# galvanika-board-2_2.net
KiCad netlist of a schematic drawn in EAGLE
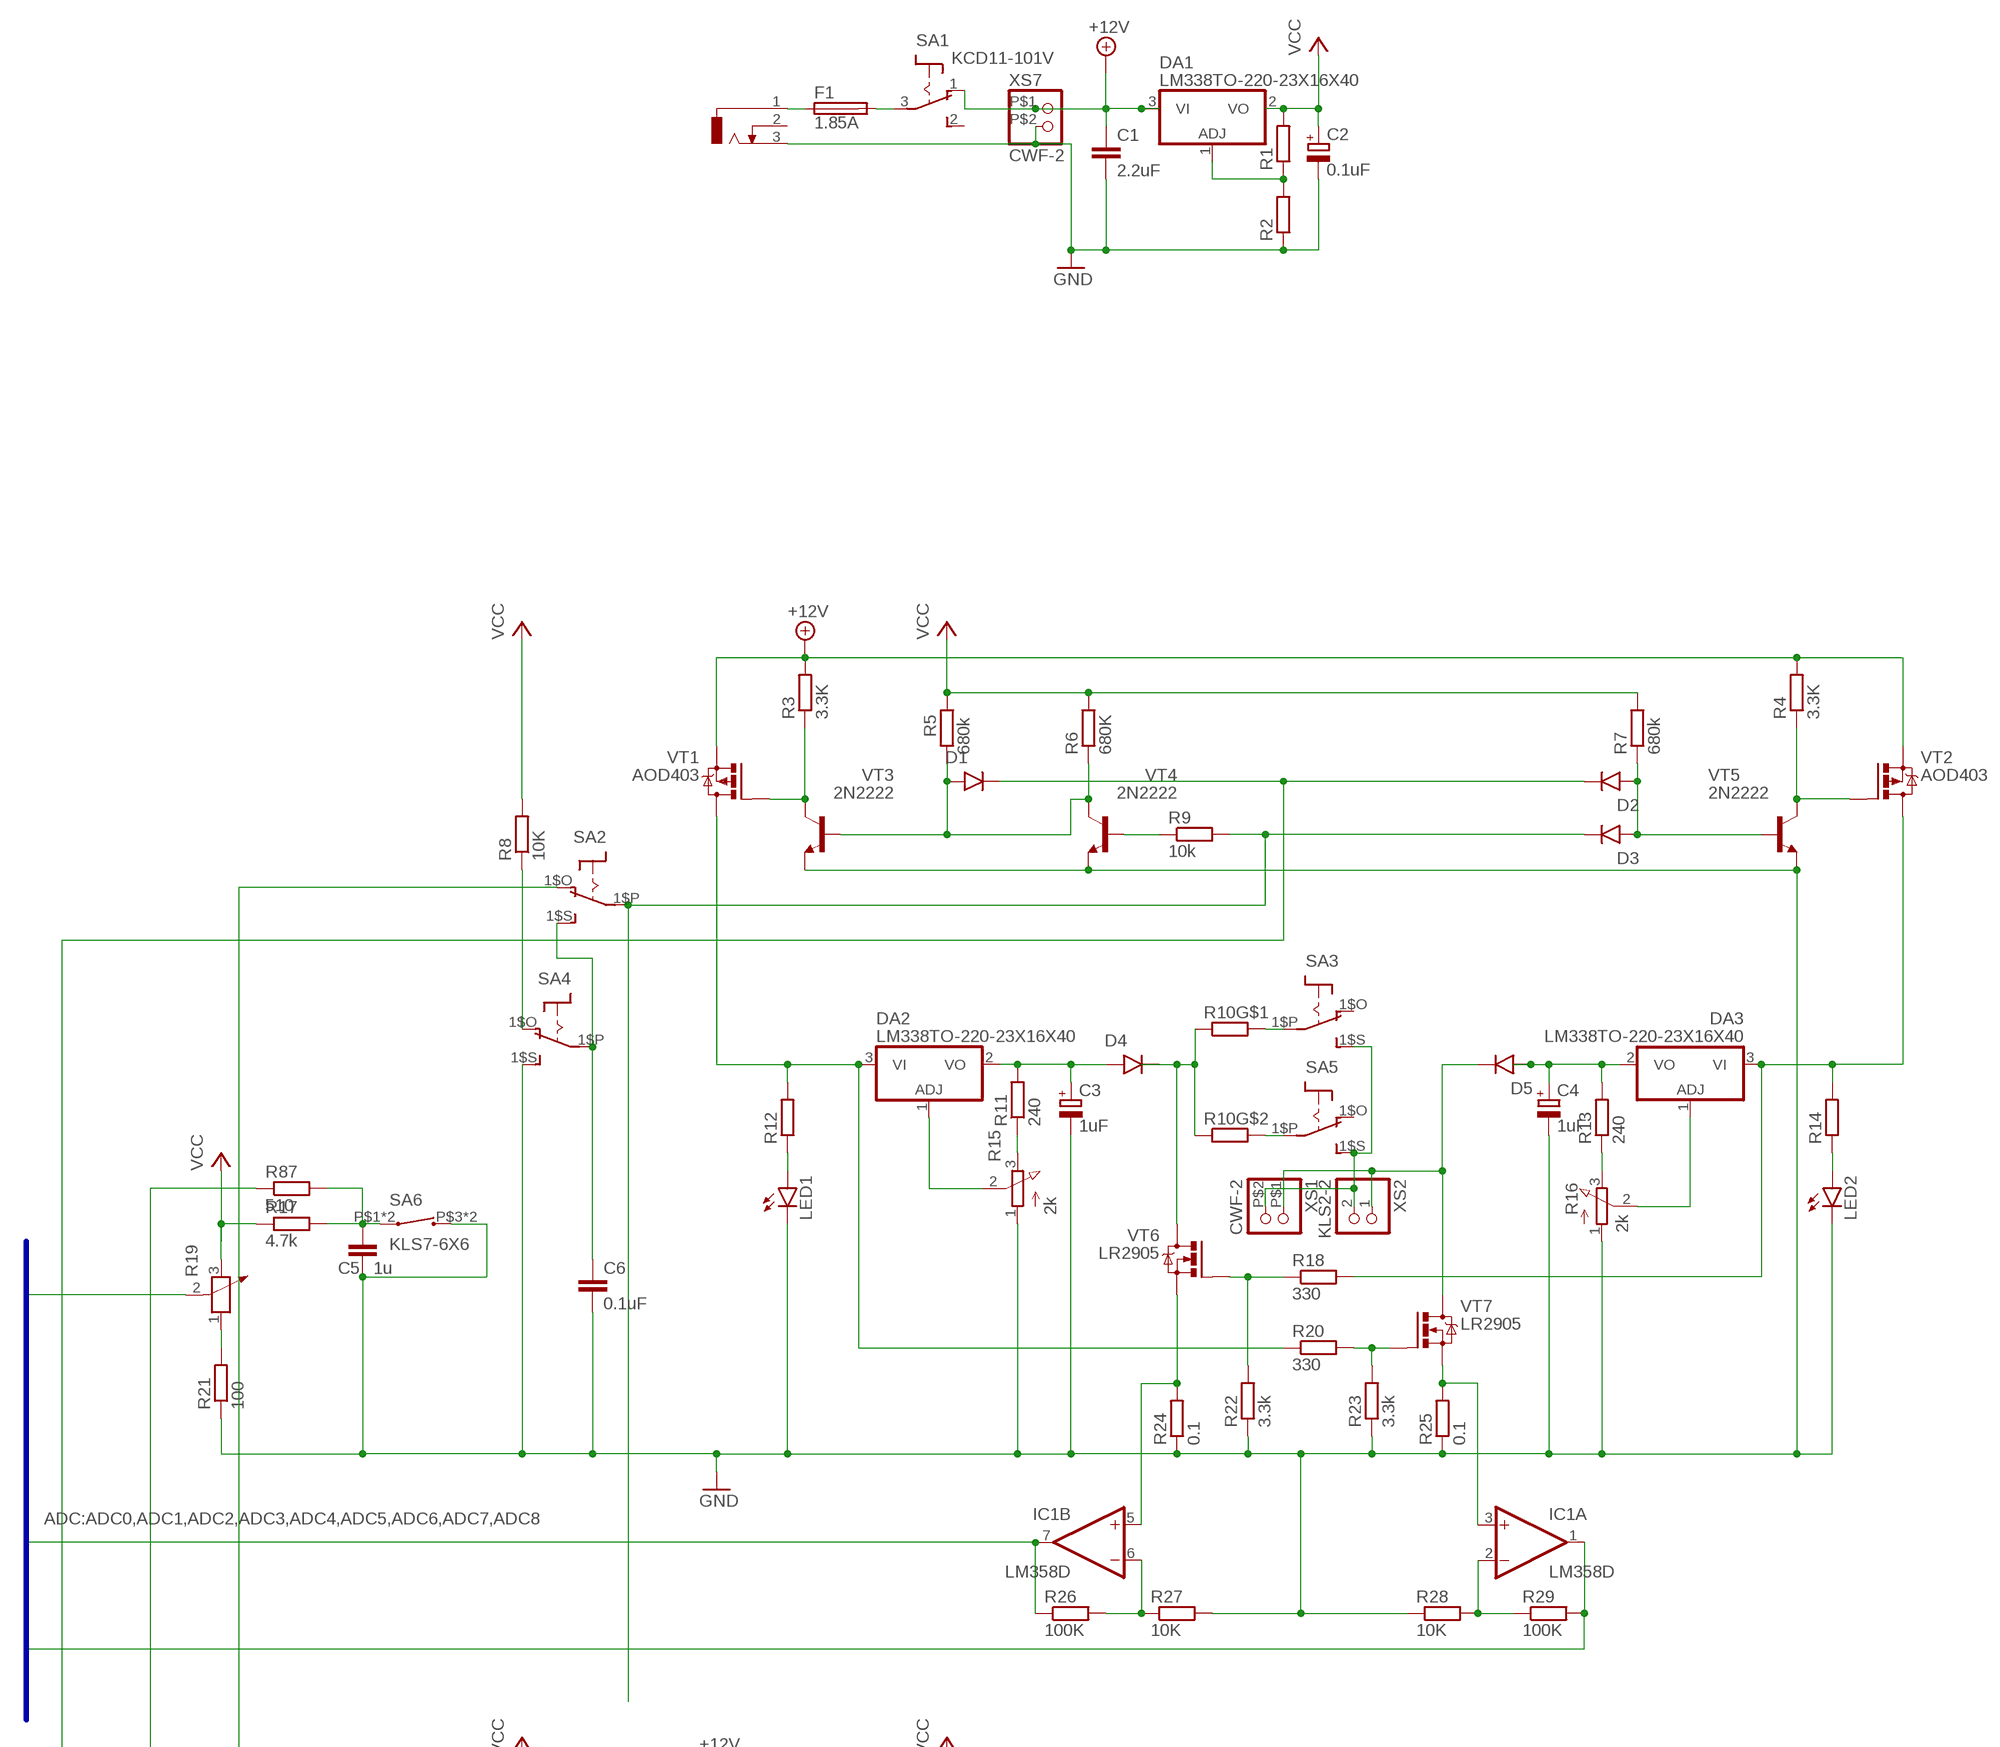
[diagram p0: schematic, sheet 1, part 1 of 2]
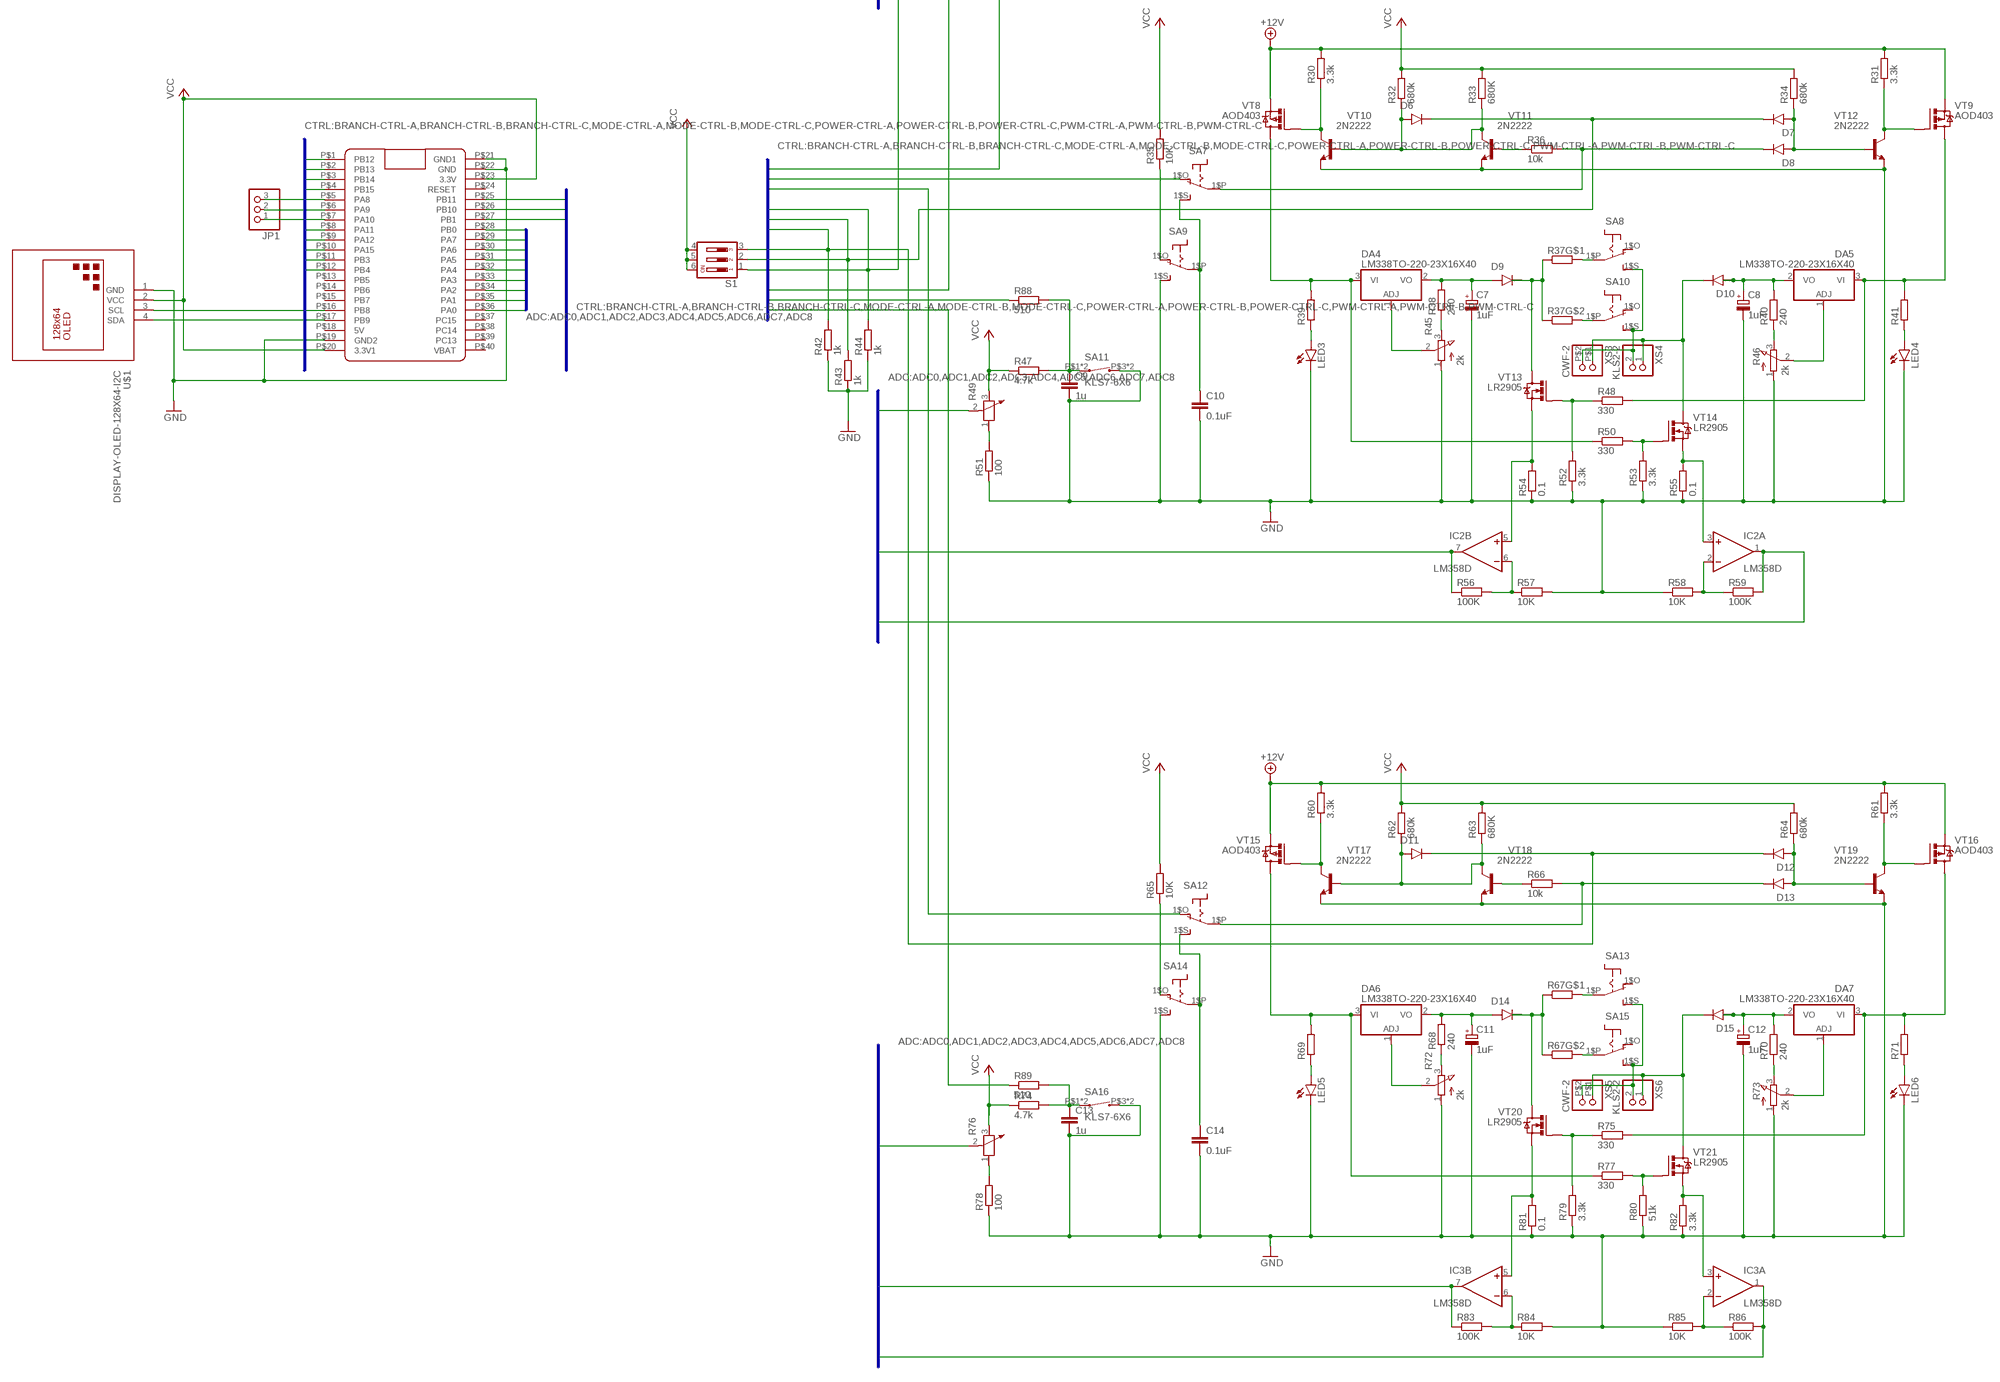
[diagram p1: schematic, sheet 1, part 2 of 2]

(export (version "E")
  (design (tool "Eeschema 10.0.6"))
  (components
    (comp (ref "C1")
      (value "2.2uF")
      (footprint "eagle-import:C025-025X050")
      (libsource (lib "eagle-import") (part "C-EU025-025X050"))
    )
    (comp (ref "C2")
      (value "0.1uF")
      (footprint "eagle-import:E2,5-5")
      (libsource (lib "eagle-import") (part "rcl_334_CPOL-EUE2.5-5"))
    )
    (comp (ref "C3")
      (value "1uF")
      (footprint "eagle-import:E5-4")
      (libsource (lib "eagle-import") (part "CPOL-EUE5-4"))
    )
    (comp (ref "C4")
      (value "1uF")
      (footprint "eagle-import:E5-4")
      (libsource (lib "eagle-import") (part "CPOL-EUE5-4"))
    )
    (comp (ref "C5")
      (value "1u")
      (footprint "eagle-import:C1206")
      (libsource (lib "eagle-import") (part "C-EUC1206"))
    )
    (comp (ref "C6")
      (value "0.1uF")
      (footprint "eagle-import:C1206")
      (libsource (lib "eagle-import") (part "C-EUC1206"))
    )
    (comp (ref "C7")
      (value "1uF")
      (footprint "eagle-import:E5-4")
      (libsource (lib "eagle-import") (part "CPOL-EUE5-4"))
    )
    (comp (ref "C8")
      (value "1uF")
      (footprint "eagle-import:E5-4")
      (libsource (lib "eagle-import") (part "CPOL-EUE5-4"))
    )
    (comp (ref "C9")
      (value "1u")
      (footprint "eagle-import:C1206")
      (libsource (lib "eagle-import") (part "C-EUC1206"))
    )
    (comp (ref "C10")
      (value "0.1uF")
      (footprint "eagle-import:C1206")
      (libsource (lib "eagle-import") (part "C-EUC1206"))
    )
    (comp (ref "C11")
      (value "1uF")
      (footprint "eagle-import:E5-4")
      (libsource (lib "eagle-import") (part "CPOL-EUE5-4"))
    )
    (comp (ref "C12")
      (value "1uF")
      (footprint "eagle-import:E5-4")
      (libsource (lib "eagle-import") (part "CPOL-EUE5-4"))
    )
    (comp (ref "C13")
      (value "1u")
      (footprint "eagle-import:C1206")
      (libsource (lib "eagle-import") (part "C-EUC1206"))
    )
    (comp (ref "C14")
      (value "0.1uF")
      (footprint "eagle-import:C1206")
      (libsource (lib "eagle-import") (part "C-EUC1206"))
    )
    (comp (ref "D1")
      (value "1N4001")
      (footprint "eagle-import:DO41-10")
      (libsource (lib "eagle-import") (part "1N4001"))
    )
    (comp (ref "D2")
      (value "1N4001")
      (footprint "eagle-import:DO41-10")
      (libsource (lib "eagle-import") (part "1N4001"))
    )
    (comp (ref "D3")
      (value "1N4001")
      (footprint "eagle-import:DO41-10")
      (libsource (lib "eagle-import") (part "1N4001"))
    )
    (comp (ref "D4")
      (value "1N4001")
      (footprint "eagle-import:DO41-10")
      (libsource (lib "eagle-import") (part "1N4001"))
    )
    (comp (ref "D5")
      (value "1N4001")
      (footprint "eagle-import:DO41-10")
      (libsource (lib "eagle-import") (part "1N4001"))
    )
    (comp (ref "D6")
      (value "1N4001")
      (footprint "eagle-import:DO41-10")
      (libsource (lib "eagle-import") (part "1N4001"))
    )
    (comp (ref "D7")
      (value "1N4001")
      (footprint "eagle-import:DO41-10")
      (libsource (lib "eagle-import") (part "1N4001"))
    )
    (comp (ref "D8")
      (value "1N4001")
      (footprint "eagle-import:DO41-10")
      (libsource (lib "eagle-import") (part "1N4001"))
    )
    (comp (ref "D9")
      (value "1N4001")
      (footprint "eagle-import:DO41-10")
      (libsource (lib "eagle-import") (part "1N4001"))
    )
    (comp (ref "D10")
      (value "1N4001")
      (footprint "eagle-import:DO41-10")
      (libsource (lib "eagle-import") (part "1N4001"))
    )
    (comp (ref "D11")
      (value "1N4001")
      (footprint "eagle-import:DO41-10")
      (libsource (lib "eagle-import") (part "1N4001"))
    )
    (comp (ref "D12")
      (value "1N4001")
      (footprint "eagle-import:DO41-10")
      (libsource (lib "eagle-import") (part "1N4001"))
    )
    (comp (ref "D13")
      (value "1N4001")
      (footprint "eagle-import:DO41-10")
      (libsource (lib "eagle-import") (part "1N4001"))
    )
    (comp (ref "D14")
      (value "1N4001")
      (footprint "eagle-import:DO41-10")
      (libsource (lib "eagle-import") (part "1N4001"))
    )
    (comp (ref "D15")
      (value "1N4001")
      (footprint "eagle-import:DO41-10")
      (libsource (lib "eagle-import") (part "1N4001"))
    )
    (comp (ref "DA1")
      (value "LM338TO-220-23X16X40")
      (footprint "eagle-import:TO220-23X16X40")
      (libsource (lib "eagle-import") (part "LM338TO-220-23X16X40"))
    )
    (comp (ref "DA2")
      (value "LM338TO-220-23X16X40")
      (footprint "eagle-import:TO220-23X16X40")
      (libsource (lib "eagle-import") (part "LM338TO-220-23X16X40"))
    )
    (comp (ref "DA3")
      (value "LM338TO-220-23X16X40")
      (footprint "eagle-import:TO220-23X16X40")
      (libsource (lib "eagle-import") (part "LM338TO-220-23X16X40"))
    )
    (comp (ref "DA4")
      (value "LM338TO-220-23X16X40")
      (footprint "eagle-import:TO220-23X16X40")
      (libsource (lib "eagle-import") (part "LM338TO-220-23X16X40"))
    )
    (comp (ref "DA5")
      (value "LM338TO-220-23X16X40")
      (footprint "eagle-import:TO220-23X16X40")
      (libsource (lib "eagle-import") (part "LM338TO-220-23X16X40"))
    )
    (comp (ref "DA6")
      (value "LM338TO-220-23X16X40")
      (footprint "eagle-import:TO220-23X16X40")
      (libsource (lib "eagle-import") (part "LM338TO-220-23X16X40"))
    )
    (comp (ref "DA7")
      (value "LM338TO-220-23X16X40")
      (footprint "eagle-import:TO220-23X16X40")
      (libsource (lib "eagle-import") (part "LM338TO-220-23X16X40"))
    )
    (comp (ref "DD1")
      (value "BLUE_PILL")
      (footprint "eagle-import:BLUE_PILL")
      (libsource (lib "eagle-import") (part "BLUE_PILL"))
    )
    (comp (ref "F1")
      (value "1.85A")
      (footprint "eagle-import:MF-R")
      (libsource (lib "eagle-import") (part "MF-R"))
    )
    (comp (ref "IC1")
      (value "LM358D")
      (footprint "eagle-import:SO08")
      (libsource (lib "eagle-import") (part "LM358D"))
    )
    (comp (ref "IC2")
      (value "LM358D")
      (footprint "eagle-import:SO08")
      (libsource (lib "eagle-import") (part "LM358D"))
    )
    (comp (ref "IC3")
      (value "LM358D")
      (footprint "eagle-import:SO08")
      (libsource (lib "eagle-import") (part "LM358D"))
    )
    (comp (ref "J1")
      (value "DCJ0303")
      (footprint "eagle-import:DCJ0303")
      (libsource (lib "eagle-import") (part "DCJ0303"))
    )
    (comp (ref "JP1")
      (value "PINHD-1X3")
      (footprint "eagle-import:1X03")
      (libsource (lib "eagle-import") (part "PINHD-1X3"))
    )
    (comp (ref "LED1")
      (value "LED3MM")
      (footprint "eagle-import:LED3MM")
      (libsource (lib "eagle-import") (part "LED3MM"))
    )
    (comp (ref "LED2")
      (value "LED3MM")
      (footprint "eagle-import:LED3MM")
      (libsource (lib "eagle-import") (part "LED3MM"))
    )
    (comp (ref "LED3")
      (value "LED3MM")
      (footprint "eagle-import:LED3MM")
      (libsource (lib "eagle-import") (part "LED3MM"))
    )
    (comp (ref "LED4")
      (value "LED3MM")
      (footprint "eagle-import:LED3MM")
      (libsource (lib "eagle-import") (part "LED3MM"))
    )
    (comp (ref "LED5")
      (value "LED3MM")
      (footprint "eagle-import:LED3MM")
      (libsource (lib "eagle-import") (part "LED3MM"))
    )
    (comp (ref "LED6")
      (value "LED3MM")
      (footprint "eagle-import:LED3MM")
      (libsource (lib "eagle-import") (part "LED3MM"))
    )
    (comp (ref "R1")
      (value "R-EU_0207/10")
      (footprint "eagle-import:0207_10")
      (libsource (lib "eagle-import") (part "R-EU_0207/10"))
    )
    (comp (ref "R2")
      (value "R-EU_0207/10")
      (footprint "eagle-import:0207_10")
      (libsource (lib "eagle-import") (part "R-EU_0207/10"))
    )
    (comp (ref "R3")
      (value "3.3K")
      (footprint "eagle-import:0207_10")
      (libsource (lib "eagle-import") (part "rcl_334_R-EU_0207/10"))
    )
    (comp (ref "R4")
      (value "3.3K")
      (footprint "eagle-import:0207_10")
      (libsource (lib "eagle-import") (part "rcl_334_R-EU_0207/10"))
    )
    (comp (ref "R5")
      (value "680k")
      (footprint "eagle-import:0207_10")
      (libsource (lib "eagle-import") (part "rcl_334_R-EU_0207/10"))
    )
    (comp (ref "R6")
      (value "680K")
      (footprint "eagle-import:0207_10")
      (libsource (lib "eagle-import") (part "rcl_334_R-EU_0207/10"))
    )
    (comp (ref "R7")
      (value "680k")
      (footprint "eagle-import:0207_10")
      (libsource (lib "eagle-import") (part "rcl_334_R-EU_0207/10"))
    )
    (comp (ref "R8")
      (value "10K")
      (footprint "eagle-import:0207_10")
      (libsource (lib "eagle-import") (part "rcl_334_R-EU_0207/10"))
    )
    (comp (ref "R9")
      (value "10k")
      (footprint "eagle-import:0207_10")
      (libsource (lib "eagle-import") (part "rcl_334_R-EU_0207/10"))
    )
    (comp (ref "R10")
      (value "SQP-5W-2")
      (footprint "eagle-import:SQP-5W-2")
      (libsource (lib "eagle-import") (part "SQP-5W-2"))
    )
    (comp (ref "R11")
      (value "240")
      (footprint "eagle-import:0207_10")
      (libsource (lib "eagle-import") (part "rcl_334_R-EU_0207/10"))
    )
    (comp (ref "R12")
      (value "R-EU_0207/10")
      (footprint "eagle-import:0207_10")
      (libsource (lib "eagle-import") (part "rcl_334_R-EU_0207/10"))
    )
    (comp (ref "R13")
      (value "240")
      (footprint "eagle-import:0207_10")
      (libsource (lib "eagle-import") (part "rcl_334_R-EU_0207/10"))
    )
    (comp (ref "R14")
      (value "R-EU_0207/10")
      (footprint "eagle-import:0207_10")
      (libsource (lib "eagle-import") (part "rcl_334_R-EU_0207/10"))
    )
    (comp (ref "R15")
      (value "2k")
      (footprint "eagle-import:3RP_1610N")
      (libsource (lib "eagle-import") (part "3RP/1610N"))
    )
    (comp (ref "R16")
      (value "2k")
      (footprint "eagle-import:3RP_1610N")
      (libsource (lib "eagle-import") (part "3RP/1610N"))
    )
    (comp (ref "R17")
      (value "4.7k")
      (footprint "eagle-import:R1206")
      (libsource (lib "eagle-import") (part "R-EU_R1206"))
    )
    (comp (ref "R18")
      (value "330")
      (footprint "eagle-import:0207_10")
      (libsource (lib "eagle-import") (part "rcl_334_R-EU_0207/10"))
    )
    (comp (ref "R19")
      (value "R0904N")
      (footprint "eagle-import:R0904N")
      (libsource (lib "eagle-import") (part "R0904N"))
    )
    (comp (ref "R20")
      (value "330")
      (footprint "eagle-import:0207_10")
      (libsource (lib "eagle-import") (part "rcl_334_R-EU_0207/10"))
    )
    (comp (ref "R21")
      (value "100")
      (footprint "eagle-import:R1206")
      (libsource (lib "eagle-import") (part "R-EU_R1206"))
    )
    (comp (ref "R22")
      (value "3.3k")
      (footprint "eagle-import:0207_10")
      (libsource (lib "eagle-import") (part "rcl_334_R-EU_0207/10"))
    )
    (comp (ref "R23")
      (value "3.3k")
      (footprint "eagle-import:0207_10")
      (libsource (lib "eagle-import") (part "rcl_334_R-EU_0207/10"))
    )
    (comp (ref "R24")
      (value "0.1")
      (footprint "eagle-import:0411_12")
      (libsource (lib "eagle-import") (part "rcl_334_R-EU_0411/12"))
    )
    (comp (ref "R25")
      (value "0.1")
      (footprint "eagle-import:0411_12")
      (libsource (lib "eagle-import") (part "rcl_334_R-EU_0411/12"))
    )
    (comp (ref "R26")
      (value "100K")
      (footprint "eagle-import:R1206")
      (libsource (lib "eagle-import") (part "rcl_334_R-EU_R1206"))
    )
    (comp (ref "R27")
      (value "10K")
      (footprint "eagle-import:R1206")
      (libsource (lib "eagle-import") (part "rcl_334_R-EU_R1206"))
    )
    (comp (ref "R28")
      (value "10K")
      (footprint "eagle-import:R1206")
      (libsource (lib "eagle-import") (part "rcl_334_R-EU_R1206"))
    )
    (comp (ref "R29")
      (value "100K")
      (footprint "eagle-import:R1206")
      (libsource (lib "eagle-import") (part "rcl_334_R-EU_R1206"))
    )
    (comp (ref "R30")
      (value "3.3k")
      (footprint "eagle-import:0207_10")
      (libsource (lib "eagle-import") (part "rcl_334_R-EU_0207/10"))
    )
    (comp (ref "R31")
      (value "3.3k")
      (footprint "eagle-import:0207_10")
      (libsource (lib "eagle-import") (part "rcl_334_R-EU_0207/10"))
    )
    (comp (ref "R32")
      (value "680k")
      (footprint "eagle-import:0207_10")
      (libsource (lib "eagle-import") (part "rcl_334_R-EU_0207/10"))
    )
    (comp (ref "R33")
      (value "680K")
      (footprint "eagle-import:0207_10")
      (libsource (lib "eagle-import") (part "rcl_334_R-EU_0207/10"))
    )
    (comp (ref "R34")
      (value "680k")
      (footprint "eagle-import:0207_10")
      (libsource (lib "eagle-import") (part "rcl_334_R-EU_0207/10"))
    )
    (comp (ref "R35")
      (value "10K")
      (footprint "eagle-import:0207_10")
      (libsource (lib "eagle-import") (part "rcl_334_R-EU_0207/10"))
    )
    (comp (ref "R36")
      (value "10k")
      (footprint "eagle-import:0207_10")
      (libsource (lib "eagle-import") (part "rcl_334_R-EU_0207/10"))
    )
    (comp (ref "R37")
      (value "SQP-5W-2")
      (footprint "eagle-import:SQP-5W-2")
      (libsource (lib "eagle-import") (part "SQP-5W-2"))
    )
    (comp (ref "R38")
      (value "240")
      (footprint "eagle-import:0207_10")
      (libsource (lib "eagle-import") (part "R-EU_0207/10"))
    )
    (comp (ref "R39")
      (value "R-EU_0207/10")
      (footprint "eagle-import:0207_10")
      (libsource (lib "eagle-import") (part "R-EU_0207/10"))
    )
    (comp (ref "R40")
      (value "240")
      (footprint "eagle-import:0207_10")
      (libsource (lib "eagle-import") (part "rcl_334_R-EU_0207/10"))
    )
    (comp (ref "R41")
      (value "R-EU_0207/10")
      (footprint "eagle-import:0207_10")
      (libsource (lib "eagle-import") (part "R-EU_0207/10"))
    )
    (comp (ref "R42")
      (value "1k")
      (footprint "eagle-import:R1206")
      (libsource (lib "eagle-import") (part "R-EU_R1206"))
    )
    (comp (ref "R43")
      (value "1k")
      (footprint "eagle-import:R1206")
      (libsource (lib "eagle-import") (part "R-EU_R1206"))
    )
    (comp (ref "R44")
      (value "1k")
      (footprint "eagle-import:R1206")
      (libsource (lib "eagle-import") (part "R-EU_R1206"))
    )
    (comp (ref "R45")
      (value "2k")
      (footprint "eagle-import:3RP_1610N")
      (libsource (lib "eagle-import") (part "3RP/1610N"))
    )
    (comp (ref "R46")
      (value "2k")
      (footprint "eagle-import:3RP_1610N")
      (libsource (lib "eagle-import") (part "3RP/1610N"))
    )
    (comp (ref "R47")
      (value "4.7k")
      (footprint "eagle-import:R1206")
      (libsource (lib "eagle-import") (part "R-EU_R1206"))
    )
    (comp (ref "R48")
      (value "330")
      (footprint "eagle-import:0207_10")
      (libsource (lib "eagle-import") (part "rcl_334_R-EU_0207/10"))
    )
    (comp (ref "R49")
      (value "R0904N")
      (footprint "eagle-import:R0904N")
      (libsource (lib "eagle-import") (part "R0904N"))
    )
    (comp (ref "R50")
      (value "330")
      (footprint "eagle-import:0207_10")
      (libsource (lib "eagle-import") (part "rcl_334_R-EU_0207/10"))
    )
    (comp (ref "R51")
      (value "100")
      (footprint "eagle-import:R1206")
      (libsource (lib "eagle-import") (part "R-EU_R1206"))
    )
    (comp (ref "R52")
      (value "3.3k")
      (footprint "eagle-import:0207_10")
      (libsource (lib "eagle-import") (part "rcl_334_R-EU_0207/10"))
    )
    (comp (ref "R53")
      (value "3.3k")
      (footprint "eagle-import:0207_10")
      (libsource (lib "eagle-import") (part "rcl_334_R-EU_0207/10"))
    )
    (comp (ref "R54")
      (value "0.1")
      (footprint "eagle-import:0411_12")
      (libsource (lib "eagle-import") (part "rcl_334_R-EU_0411/12"))
    )
    (comp (ref "R55")
      (value "0.1")
      (footprint "eagle-import:0411_12")
      (libsource (lib "eagle-import") (part "rcl_334_R-EU_0411/12"))
    )
    (comp (ref "R56")
      (value "100K")
      (footprint "eagle-import:R1206")
      (libsource (lib "eagle-import") (part "rcl_334_R-EU_R1206"))
    )
    (comp (ref "R57")
      (value "10K")
      (footprint "eagle-import:R1206")
      (libsource (lib "eagle-import") (part "rcl_334_R-EU_R1206"))
    )
    (comp (ref "R58")
      (value "10K")
      (footprint "eagle-import:R1206")
      (libsource (lib "eagle-import") (part "rcl_334_R-EU_R1206"))
    )
    (comp (ref "R59")
      (value "100K")
      (footprint "eagle-import:R1206")
      (libsource (lib "eagle-import") (part "rcl_334_R-EU_R1206"))
    )
    (comp (ref "R60")
      (value "3.3k")
      (footprint "eagle-import:0207_10")
      (libsource (lib "eagle-import") (part "rcl_334_R-EU_0207/10"))
    )
    (comp (ref "R61")
      (value "3.3k")
      (footprint "eagle-import:0207_10")
      (libsource (lib "eagle-import") (part "rcl_334_R-EU_0207/10"))
    )
    (comp (ref "R62")
      (value "680k")
      (footprint "eagle-import:0207_10")
      (libsource (lib "eagle-import") (part "rcl_334_R-EU_0207/10"))
    )
    (comp (ref "R63")
      (value "680K")
      (footprint "eagle-import:0207_10")
      (libsource (lib "eagle-import") (part "rcl_334_R-EU_0207/10"))
    )
    (comp (ref "R64")
      (value "680k")
      (footprint "eagle-import:0207_10")
      (libsource (lib "eagle-import") (part "rcl_334_R-EU_0207/10"))
    )
    (comp (ref "R65")
      (value "10K")
      (footprint "eagle-import:0207_10")
      (libsource (lib "eagle-import") (part "rcl_334_R-EU_0207/10"))
    )
    (comp (ref "R66")
      (value "10k")
      (footprint "eagle-import:0207_10")
      (libsource (lib "eagle-import") (part "rcl_334_R-EU_0207/10"))
    )
    (comp (ref "R67")
      (value "SQP-5W-2")
      (footprint "eagle-import:SQP-5W-2")
      (libsource (lib "eagle-import") (part "SQP-5W-2"))
    )
    (comp (ref "R68")
      (value "240")
      (footprint "eagle-import:0207_10")
      (libsource (lib "eagle-import") (part "rcl_334_R-EU_0207/10"))
    )
    (comp (ref "R69")
      (value "R-EU_0207/10")
      (footprint "eagle-import:0207_10")
      (libsource (lib "eagle-import") (part "rcl_334_R-EU_0207/10"))
    )
    (comp (ref "R70")
      (value "240")
      (footprint "eagle-import:0207_10")
      (libsource (lib "eagle-import") (part "rcl_334_R-EU_0207/10"))
    )
    (comp (ref "R71")
      (value "R-EU_0207/10")
      (footprint "eagle-import:0207_10")
      (libsource (lib "eagle-import") (part "rcl_334_R-EU_0207/10"))
    )
    (comp (ref "R72")
      (value "2k")
      (footprint "eagle-import:3RP_1610N")
      (libsource (lib "eagle-import") (part "3RP/1610N"))
    )
    (comp (ref "R73")
      (value "2k")
      (footprint "eagle-import:3RP_1610N")
      (libsource (lib "eagle-import") (part "3RP/1610N"))
    )
    (comp (ref "R74")
      (value "4.7k")
      (footprint "eagle-import:R1206")
      (libsource (lib "eagle-import") (part "R-EU_R1206"))
    )
    (comp (ref "R75")
      (value "330")
      (footprint "eagle-import:0207_10")
      (libsource (lib "eagle-import") (part "rcl_334_R-EU_0207/10"))
    )
    (comp (ref "R76")
      (value "R0904N")
      (footprint "eagle-import:R0904N")
      (libsource (lib "eagle-import") (part "R0904N"))
    )
    (comp (ref "R77")
      (value "330")
      (footprint "eagle-import:0207_10")
      (libsource (lib "eagle-import") (part "rcl_334_R-EU_0207/10"))
    )
    (comp (ref "R78")
      (value "100")
      (footprint "eagle-import:R1206")
      (libsource (lib "eagle-import") (part "R-EU_R1206"))
    )
    (comp (ref "R79")
      (value "3.3k")
      (footprint "eagle-import:0207_10")
      (libsource (lib "eagle-import") (part "rcl_334_R-EU_0207/10"))
    )
    (comp (ref "R80")
      (value "51k")
      (footprint "eagle-import:0207_10")
      (libsource (lib "eagle-import") (part "rcl_334_R-EU_0207/10"))
    )
    (comp (ref "R81")
      (value "0.1")
      (footprint "eagle-import:0411_12")
      (libsource (lib "eagle-import") (part "rcl_334_R-EU_0411/12"))
    )
    (comp (ref "R82")
      (value "3.3k")
      (footprint "eagle-import:0411_12")
      (libsource (lib "eagle-import") (part "rcl_334_R-EU_0411/12"))
    )
    (comp (ref "R83")
      (value "100K")
      (footprint "eagle-import:R1206")
      (libsource (lib "eagle-import") (part "rcl_334_R-EU_R1206"))
    )
    (comp (ref "R84")
      (value "10K")
      (footprint "eagle-import:R1206")
      (libsource (lib "eagle-import") (part "rcl_334_R-EU_R1206"))
    )
    (comp (ref "R85")
      (value "10K")
      (footprint "eagle-import:R1206")
      (libsource (lib "eagle-import") (part "rcl_334_R-EU_R1206"))
    )
    (comp (ref "R86")
      (value "100K")
      (footprint "eagle-import:R1206")
      (libsource (lib "eagle-import") (part "rcl_334_R-EU_R1206"))
    )
    (comp (ref "R87")
      (value "510")
      (footprint "eagle-import:R1206")
      (libsource (lib "eagle-import") (part "R-EU_R1206"))
    )
    (comp (ref "R88")
      (value "510")
      (footprint "eagle-import:R1206")
      (libsource (lib "eagle-import") (part "R-EU_R1206"))
    )
    (comp (ref "R89")
      (value "510")
      (footprint "eagle-import:R1206")
      (libsource (lib "eagle-import") (part "R-EU_R1206"))
    )
    (comp (ref "S1")
      (value "DS03")
      (footprint "eagle-import:DS-03")
      (libsource (lib "eagle-import") (part "DS03"))
    )
    (comp (ref "SA1")
      (value "KCD11-101V")
      (footprint "eagle-import:KCD11-101-V")
      (libsource (lib "eagle-import") (part "KCD11-101V"))
    )
    (comp (ref "SA2")
      (value "SS12D00DIP")
      (footprint "eagle-import:SS12D00")
      (libsource (lib "eagle-import") (part "SS12D00DIP"))
    )
    (comp (ref "SA3")
      (value "SS12D00DIP")
      (footprint "eagle-import:SS12D00")
      (libsource (lib "eagle-import") (part "SS12D00DIP"))
    )
    (comp (ref "SA4")
      (value "SS12D00DIP")
      (footprint "eagle-import:SS12D00")
      (libsource (lib "eagle-import") (part "SS12D00DIP"))
    )
    (comp (ref "SA5")
      (value "SS12D00DIP")
      (footprint "eagle-import:SS12D00")
      (libsource (lib "eagle-import") (part "SS12D00DIP"))
    )
    (comp (ref "SA6")
      (value "KLS7-6X6")
      (footprint "eagle-import:KLS7-6X6")
      (libsource (lib "eagle-import") (part "KLS7-6X6"))
    )
    (comp (ref "SA7")
      (value "SS12D00DIP")
      (footprint "eagle-import:SS12D00")
      (libsource (lib "eagle-import") (part "SS12D00DIP"))
    )
    (comp (ref "SA8")
      (value "SS12D00DIP")
      (footprint "eagle-import:SS12D00")
      (libsource (lib "eagle-import") (part "SS12D00DIP"))
    )
    (comp (ref "SA9")
      (value "SS12D00DIP")
      (footprint "eagle-import:SS12D00")
      (libsource (lib "eagle-import") (part "SS12D00DIP"))
    )
    (comp (ref "SA10")
      (value "SS12D00DIP")
      (footprint "eagle-import:SS12D00")
      (libsource (lib "eagle-import") (part "SS12D00DIP"))
    )
    (comp (ref "SA11")
      (value "KLS7-6X6")
      (footprint "eagle-import:KLS7-6X6")
      (libsource (lib "eagle-import") (part "KLS7-6X6"))
    )
    (comp (ref "SA12")
      (value "SS12D00DIP")
      (footprint "eagle-import:SS12D00")
      (libsource (lib "eagle-import") (part "SS12D00DIP"))
    )
    (comp (ref "SA13")
      (value "SS12D00DIP")
      (footprint "eagle-import:SS12D00")
      (libsource (lib "eagle-import") (part "SS12D00DIP"))
    )
    (comp (ref "SA14")
      (value "SS12D00DIP")
      (footprint "eagle-import:SS12D00")
      (libsource (lib "eagle-import") (part "SS12D00DIP"))
    )
    (comp (ref "SA15")
      (value "SS12D00DIP")
      (footprint "eagle-import:SS12D00")
      (libsource (lib "eagle-import") (part "SS12D00DIP"))
    )
    (comp (ref "SA16")
      (value "KLS7-6X6")
      (footprint "eagle-import:KLS7-6X6")
      (libsource (lib "eagle-import") (part "KLS7-6X6"))
    )
    (comp (ref "U$1")
      (value "DISPLAY-OLED-128X64-I2C")
      (footprint "eagle-import:DISPLAY-OLED-128X64-I2C")
      (libsource (lib "eagle-import") (part "DISPLAY-OLED-128X64-I2C"))
    )
    (comp (ref "VT1")
      (value "AOD403")
      (footprint "eagle-import:TO252")
      (libsource (lib "eagle-import") (part "AOD403"))
    )
    (comp (ref "VT2")
      (value "AOD403")
      (footprint "eagle-import:TO252")
      (libsource (lib "eagle-import") (part "AOD403"))
    )
    (comp (ref "VT3")
      (value "2N2222")
      (footprint "eagle-import:TO92")
      (libsource (lib "eagle-import") (part "2N2222"))
    )
    (comp (ref "VT4")
      (value "2N2222")
      (footprint "eagle-import:TO92")
      (libsource (lib "eagle-import") (part "2N2222"))
    )
    (comp (ref "VT5")
      (value "2N2222")
      (footprint "eagle-import:TO92")
      (libsource (lib "eagle-import") (part "2N2222"))
    )
    (comp (ref "VT6")
      (value "LR2905")
      (footprint "eagle-import:TO252")
      (libsource (lib "eagle-import") (part "LR2905"))
    )
    (comp (ref "VT7")
      (value "LR2905")
      (footprint "eagle-import:TO252")
      (libsource (lib "eagle-import") (part "LR2905"))
    )
    (comp (ref "VT8")
      (value "AOD403")
      (footprint "eagle-import:TO252")
      (libsource (lib "eagle-import") (part "AOD403"))
    )
    (comp (ref "VT9")
      (value "AOD403")
      (footprint "eagle-import:TO252")
      (libsource (lib "eagle-import") (part "AOD403"))
    )
    (comp (ref "VT10")
      (value "2N2222")
      (footprint "eagle-import:TO92")
      (libsource (lib "eagle-import") (part "2N2222"))
    )
    (comp (ref "VT11")
      (value "2N2222")
      (footprint "eagle-import:TO92")
      (libsource (lib "eagle-import") (part "2N2222"))
    )
    (comp (ref "VT12")
      (value "2N2222")
      (footprint "eagle-import:TO92")
      (libsource (lib "eagle-import") (part "2N2222"))
    )
    (comp (ref "VT13")
      (value "LR2905")
      (footprint "eagle-import:TO252")
      (libsource (lib "eagle-import") (part "LR2905"))
    )
    (comp (ref "VT14")
      (value "LR2905")
      (footprint "eagle-import:TO252")
      (libsource (lib "eagle-import") (part "LR2905"))
    )
    (comp (ref "VT15")
      (value "AOD403")
      (footprint "eagle-import:TO252")
      (libsource (lib "eagle-import") (part "AOD403"))
    )
    (comp (ref "VT16")
      (value "AOD403")
      (footprint "eagle-import:TO252")
      (libsource (lib "eagle-import") (part "AOD403"))
    )
    (comp (ref "VT17")
      (value "2N2222")
      (footprint "eagle-import:TO92")
      (libsource (lib "eagle-import") (part "2N2222"))
    )
    (comp (ref "VT18")
      (value "2N2222")
      (footprint "eagle-import:TO92")
      (libsource (lib "eagle-import") (part "2N2222"))
    )
    (comp (ref "VT19")
      (value "2N2222")
      (footprint "eagle-import:TO92")
      (libsource (lib "eagle-import") (part "2N2222"))
    )
    (comp (ref "VT20")
      (value "LR2905")
      (footprint "eagle-import:TO252")
      (libsource (lib "eagle-import") (part "LR2905"))
    )
    (comp (ref "VT21")
      (value "LR2905")
      (footprint "eagle-import:TO252")
      (libsource (lib "eagle-import") (part "LR2905"))
    )
    (comp (ref "XS1")
      (value "CWF-2")
      (footprint "eagle-import:CWF-2")
      (libsource (lib "eagle-import") (part "CWF-2"))
    )
    (comp (ref "XS2")
      (value "KLS2-2")
      (footprint "eagle-import:KLS2-2")
      (libsource (lib "eagle-import") (part "KLS2-2"))
    )
    (comp (ref "XS3")
      (value "CWF-2")
      (footprint "eagle-import:CWF-2")
      (libsource (lib "eagle-import") (part "CWF-2"))
    )
    (comp (ref "XS4")
      (value "KLS2-2")
      (footprint "eagle-import:KLS2-2")
      (libsource (lib "eagle-import") (part "KLS2-2"))
    )
    (comp (ref "XS5")
      (value "CWF-2")
      (footprint "eagle-import:CWF-2")
      (libsource (lib "eagle-import") (part "CWF-2"))
    )
    (comp (ref "XS6")
      (value "KLS2-2")
      (footprint "eagle-import:KLS2-2")
      (libsource (lib "eagle-import") (part "KLS2-2"))
    )
    (comp (ref "XS7")
      (value "CWF-2")
      (footprint "eagle-import:CWF-2")
      (libsource (lib "eagle-import") (part "CWF-2"))
    )
  )
  (nets
    (net (code "3") (name "+12V") (class "Default")
      (node (ref "C1") (pin "1") (pinfunction "1_1") (pintype "passive"))
      (node (ref "DA1") (pin "3") (pinfunction "VI_3") (pintype "input"))
      (node (ref "R3") (pin "2") (pinfunction "2_2") (pintype "passive"))
      (node (ref "R30") (pin "2") (pinfunction "2_2") (pintype "passive"))
      (node (ref "R31") (pin "2") (pinfunction "2_2") (pintype "passive"))
      (node (ref "R4") (pin "2") (pinfunction "2_2") (pintype "passive"))
      (node (ref "R60") (pin "2") (pinfunction "2_2") (pintype "passive"))
      (node (ref "R61") (pin "2") (pinfunction "2_2") (pintype "passive"))
      (node (ref "SA1") (pin "1") (pinfunction "O_1") (pintype "passive"))
      (node (ref "VT1") (pin "2") (pinfunction "S_2") (pintype "passive"))
      (node (ref "VT15") (pin "2") (pinfunction "S_2") (pintype "passive"))
      (node (ref "VT16") (pin "2") (pinfunction "S_2") (pintype "passive"))
      (node (ref "VT2") (pin "2") (pinfunction "S_2") (pintype "passive"))
      (node (ref "VT8") (pin "2") (pinfunction "S_2") (pintype "passive"))
      (node (ref "VT9") (pin "2") (pinfunction "S_2") (pintype "passive"))
      (node (ref "XS7") (pin "P$1") (pinfunction "1_P$1") (pintype "passive"))
    )
    (net (code "4") (name "/ADC0") (class "Default")
      (node (ref "DD1") (pin "P$36") (pinfunction "PA0_P$36") (pintype "bidirectional"))
      (node (ref "R19") (pin "2") (pinfunction "3_2") (pintype "passive"))
    )
    (net (code "5") (name "/ADC1") (class "Default")
      (node (ref "DD1") (pin "P$35") (pinfunction "PA1_P$35") (pintype "bidirectional"))
      (node (ref "R49") (pin "2") (pinfunction "3_2") (pintype "passive"))
    )
    (net (code "6") (name "/ADC2") (class "Default")
      (node (ref "DD1") (pin "P$34") (pinfunction "PA2_P$34") (pintype "bidirectional"))
      (node (ref "IC1") (pin "7") (pinfunction "OUT_7") (pintype "output"))
      (node (ref "R26") (pin "1") (pinfunction "1_1") (pintype "passive"))
    )
    (net (code "7") (name "/ADC3") (class "Default")
      (node (ref "DD1") (pin "P$33") (pinfunction "PA3_P$33") (pintype "bidirectional"))
      (node (ref "IC1") (pin "1") (pinfunction "OUT_1") (pintype "output"))
      (node (ref "R29") (pin "2") (pinfunction "2_2") (pintype "passive"))
    )
    (net (code "8") (name "/ADC4") (class "Default")
      (node (ref "DD1") (pin "P$32") (pinfunction "PA4_P$32") (pintype "bidirectional"))
      (node (ref "R76") (pin "2") (pinfunction "3_2") (pintype "passive"))
    )
    (net (code "9") (name "/ADC5") (class "Default")
      (node (ref "DD1") (pin "P$31") (pinfunction "PA5_P$31") (pintype "bidirectional"))
      (node (ref "IC2") (pin "1") (pinfunction "OUT_1") (pintype "output"))
      (node (ref "R59") (pin "2") (pinfunction "2_2") (pintype "passive"))
    )
    (net (code "10") (name "/ADC6") (class "Default")
      (node (ref "DD1") (pin "P$30") (pinfunction "PA6_P$30") (pintype "bidirectional"))
      (node (ref "IC2") (pin "7") (pinfunction "OUT_7") (pintype "output"))
      (node (ref "R56") (pin "1") (pinfunction "1_1") (pintype "passive"))
    )
    (net (code "11") (name "/ADC7") (class "Default")
      (node (ref "DD1") (pin "P$29") (pinfunction "PA7_P$29") (pintype "bidirectional"))
      (node (ref "IC3") (pin "7") (pinfunction "OUT_7") (pintype "output"))
      (node (ref "R83") (pin "1") (pinfunction "1_1") (pintype "passive"))
    )
    (net (code "12") (name "/ADC8") (class "Default")
      (node (ref "DD1") (pin "P$28") (pinfunction "PB0_P$28") (pintype "bidirectional"))
      (node (ref "IC3") (pin "1") (pinfunction "OUT_1") (pintype "output"))
      (node (ref "R86") (pin "2") (pinfunction "2_2") (pintype "passive"))
    )
    (net (code "13") (name "/BRANCH-CTRL-A") (class "Default")
      (node (ref "D3") (pin "C") (pinfunction "CATHODE_C") (pintype "passive"))
      (node (ref "DD1") (pin "P$9") (pinfunction "PA12_P$9") (pintype "bidirectional"))
      (node (ref "R9") (pin "2") (pinfunction "2_2") (pintype "passive"))
      (node (ref "SA2") (pin "1$P") (pinfunction "P_1$P") (pintype "passive"))
    )
    (net (code "14") (name "/BRANCH-CTRL-B") (class "Default")
      (node (ref "D8") (pin "C") (pinfunction "CATHODE_C") (pintype "passive"))
      (node (ref "DD1") (pin "P$8") (pinfunction "PA11_P$8") (pintype "bidirectional"))
      (node (ref "R36") (pin "2") (pinfunction "2_2") (pintype "passive"))
      (node (ref "SA7") (pin "1$P") (pinfunction "P_1$P") (pintype "passive"))
    )
    (net (code "15") (name "/BRANCH-CTRL-C") (class "Default")
      (node (ref "D13") (pin "C") (pinfunction "CATHODE_C") (pintype "passive"))
      (node (ref "DD1") (pin "P$4") (pinfunction "PB15_P$4") (pintype "bidirectional"))
      (node (ref "R66") (pin "2") (pinfunction "2_2") (pintype "passive"))
      (node (ref "SA12") (pin "1$P") (pinfunction "P_1$P") (pintype "passive"))
    )
    (net (code "16") (name "/MODE-CTRL-A") (class "Default")
      (node (ref "DD1") (pin "P$12") (pinfunction "PB4_P$12") (pintype "bidirectional"))
      (node (ref "R87") (pin "1") (pinfunction "1_1") (pintype "passive"))
    )
    (net (code "17") (name "/MODE-CTRL-B") (class "Default")
      (node (ref "DD1") (pin "P$11") (pinfunction "PB3_P$11") (pintype "bidirectional"))
      (node (ref "R88") (pin "1") (pinfunction "1_1") (pintype "passive"))
    )
    (net (code "18") (name "/MODE-CTRL-C") (class "Default")
      (node (ref "DD1") (pin "P$10") (pinfunction "PA15_P$10") (pintype "bidirectional"))
      (node (ref "R89") (pin "1") (pinfunction "1_1") (pintype "passive"))
    )
    (net (code "19") (name "/POWER-CTRL-A") (class "Default")
      (node (ref "D1") (pin "C") (pinfunction "CATHODE_C") (pintype "passive"))
      (node (ref "D2") (pin "C") (pinfunction "CATHODE_C") (pintype "passive"))
      (node (ref "DD1") (pin "P$27") (pinfunction "PB1_P$27") (pintype "bidirectional"))
      (node (ref "R44") (pin "2") (pinfunction "2_2") (pintype "passive"))
      (node (ref "S1") (pin "1") (pinfunction "1_1") (pintype "passive"))
    )
    (net (code "20") (name "/POWER-CTRL-B") (class "Default")
      (node (ref "D6") (pin "C") (pinfunction "CATHODE_C") (pintype "passive"))
      (node (ref "D7") (pin "C") (pinfunction "CATHODE_C") (pintype "passive"))
      (node (ref "DD1") (pin "P$26") (pinfunction "PB10_P$26") (pintype "bidirectional"))
      (node (ref "R43") (pin "2") (pinfunction "2_2") (pintype "passive"))
      (node (ref "S1") (pin "2") (pinfunction "2_2") (pintype "passive"))
    )
    (net (code "21") (name "/POWER-CTRL-C") (class "Default")
      (node (ref "D11") (pin "C") (pinfunction "CATHODE_C") (pintype "passive"))
      (node (ref "D12") (pin "C") (pinfunction "CATHODE_C") (pintype "passive"))
      (node (ref "DD1") (pin "P$25") (pinfunction "PB11_P$25") (pintype "bidirectional"))
      (node (ref "R42") (pin "2") (pinfunction "2_2") (pintype "passive"))
      (node (ref "S1") (pin "3") (pinfunction "3_3") (pintype "passive"))
    )
    (net (code "22") (name "/PWM-CTRL-A") (class "Default")
      (node (ref "DD1") (pin "P$2") (pinfunction "PB13_P$2") (pintype "bidirectional"))
      (node (ref "SA2") (pin "1$O") (pinfunction "O_1$O") (pintype "passive"))
    )
    (net (code "23") (name "/PWM-CTRL-B") (class "Default")
      (node (ref "DD1") (pin "P$3") (pinfunction "PB14_P$3") (pintype "bidirectional"))
      (node (ref "SA7") (pin "1$O") (pinfunction "O_1$O") (pintype "passive"))
    )
    (net (code "24") (name "/PWM-CTRL-C") (class "Default")
      (node (ref "DD1") (pin "P$1") (pinfunction "PB12_P$1") (pintype "bidirectional"))
      (node (ref "SA12") (pin "1$O") (pinfunction "O_1$O") (pintype "passive"))
    )
    (net (code "27") (name "GND") (class "Default")
      (node (ref "C1") (pin "2") (pinfunction "2_2") (pintype "passive"))
      (node (ref "C10") (pin "2") (pinfunction "2_2") (pintype "passive"))
      (node (ref "C11") (pin "-") (pinfunction "-_-") (pintype "passive"))
      (node (ref "C12") (pin "-") (pinfunction "-_-") (pintype "passive"))
      (node (ref "C13") (pin "2") (pinfunction "2_2") (pintype "passive"))
      (node (ref "C14") (pin "2") (pinfunction "2_2") (pintype "passive"))
      (node (ref "C2") (pin "-") (pinfunction "-_-") (pintype "passive"))
      (node (ref "C3") (pin "-") (pinfunction "-_-") (pintype "passive"))
      (node (ref "C4") (pin "-") (pinfunction "-_-") (pintype "passive"))
      (node (ref "C5") (pin "2") (pinfunction "2_2") (pintype "passive"))
      (node (ref "C6") (pin "2") (pinfunction "2_2") (pintype "passive"))
      (node (ref "C7") (pin "-") (pinfunction "-_-") (pintype "passive"))
      (node (ref "C8") (pin "-") (pinfunction "-_-") (pintype "passive"))
      (node (ref "C9") (pin "2") (pinfunction "2_2") (pintype "passive"))
      (node (ref "DD1") (pin "P$19") (pinfunction "GND2_P$19") (pintype "bidirectional"))
      (node (ref "DD1") (pin "P$21") (pinfunction "GND1_P$21") (pintype "power_in"))
      (node (ref "DD1") (pin "P$22") (pinfunction "GND_P$22") (pintype "bidirectional"))
      (node (ref "J1") (pin "3") (pinfunction "3_3") (pintype "passive"))
      (node (ref "LED1") (pin "K") (pinfunction "C_K") (pintype "passive"))
      (node (ref "LED2") (pin "K") (pinfunction "C_K") (pintype "passive"))
      (node (ref "LED3") (pin "K") (pinfunction "C_K") (pintype "passive"))
      (node (ref "LED4") (pin "K") (pinfunction "C_K") (pintype "passive"))
      (node (ref "LED5") (pin "K") (pinfunction "C_K") (pintype "passive"))
      (node (ref "LED6") (pin "K") (pinfunction "C_K") (pintype "passive"))
      (node (ref "R15") (pin "1") (pinfunction "A_1") (pintype "passive"))
      (node (ref "R16") (pin "1") (pinfunction "A_1") (pintype "passive"))
      (node (ref "R2") (pin "1") (pinfunction "1_1") (pintype "passive"))
      (node (ref "R21") (pin "1") (pinfunction "1_1") (pintype "passive"))
      (node (ref "R22") (pin "1") (pinfunction "1_1") (pintype "passive"))
      (node (ref "R23") (pin "1") (pinfunction "1_1") (pintype "passive"))
      (node (ref "R24") (pin "1") (pinfunction "1_1") (pintype "passive"))
      (node (ref "R25") (pin "1") (pinfunction "1_1") (pintype "passive"))
      (node (ref "R27") (pin "2") (pinfunction "2_2") (pintype "passive"))
      (node (ref "R28") (pin "1") (pinfunction "1_1") (pintype "passive"))
      (node (ref "R42") (pin "1") (pinfunction "1_1") (pintype "passive"))
      (node (ref "R43") (pin "1") (pinfunction "1_1") (pintype "passive"))
      (node (ref "R44") (pin "1") (pinfunction "1_1") (pintype "passive"))
      (node (ref "R45") (pin "1") (pinfunction "A_1") (pintype "passive"))
      (node (ref "R46") (pin "1") (pinfunction "A_1") (pintype "passive"))
      (node (ref "R51") (pin "1") (pinfunction "1_1") (pintype "passive"))
      (node (ref "R52") (pin "1") (pinfunction "1_1") (pintype "passive"))
      (node (ref "R53") (pin "1") (pinfunction "1_1") (pintype "passive"))
      (node (ref "R54") (pin "1") (pinfunction "1_1") (pintype "passive"))
      (node (ref "R55") (pin "1") (pinfunction "1_1") (pintype "passive"))
      (node (ref "R57") (pin "2") (pinfunction "2_2") (pintype "passive"))
      (node (ref "R58") (pin "1") (pinfunction "1_1") (pintype "passive"))
      (node (ref "R72") (pin "1") (pinfunction "A_1") (pintype "passive"))
      (node (ref "R73") (pin "1") (pinfunction "A_1") (pintype "passive"))
      (node (ref "R78") (pin "1") (pinfunction "1_1") (pintype "passive"))
      (node (ref "R79") (pin "1") (pinfunction "1_1") (pintype "passive"))
      (node (ref "R80") (pin "1") (pinfunction "1_1") (pintype "passive"))
      (node (ref "R81") (pin "1") (pinfunction "1_1") (pintype "passive"))
      (node (ref "R82") (pin "1") (pinfunction "1_1") (pintype "passive"))
      (node (ref "R84") (pin "2") (pinfunction "2_2") (pintype "passive"))
      (node (ref "R85") (pin "1") (pinfunction "1_1") (pintype "passive"))
      (node (ref "SA11") (pin "P$3") (pinfunction "2_P$3") (pintype "passive"))
      (node (ref "SA11") (pin "P$4") (pinfunction "2_P$4") (pintype "passive"))
      (node (ref "SA14") (pin "1$S") (pinfunction "S_1$S") (pintype "passive"))
      (node (ref "SA16") (pin "P$3") (pinfunction "2_P$3") (pintype "passive"))
      (node (ref "SA16") (pin "P$4") (pinfunction "2_P$4") (pintype "passive"))
      (node (ref "SA4") (pin "1$S") (pinfunction "S_1$S") (pintype "passive"))
      (node (ref "SA6") (pin "P$3") (pinfunction "2_P$3") (pintype "passive"))
      (node (ref "SA6") (pin "P$4") (pinfunction "2_P$4") (pintype "passive"))
      (node (ref "SA9") (pin "1$S") (pinfunction "S_1$S") (pintype "passive"))
      (node (ref "U$1") (pin "1") (pinfunction "GND_1") (pintype "power_in"))
      (node (ref "VT10") (pin "3") (pinfunction "E_3") (pintype "passive"))
      (node (ref "VT11") (pin "3") (pinfunction "E_3") (pintype "passive"))
      (node (ref "VT12") (pin "3") (pinfunction "E_3") (pintype "passive"))
      (node (ref "VT17") (pin "3") (pinfunction "E_3") (pintype "passive"))
      (node (ref "VT18") (pin "3") (pinfunction "E_3") (pintype "passive"))
      (node (ref "VT19") (pin "3") (pinfunction "E_3") (pintype "passive"))
      (node (ref "VT3") (pin "3") (pinfunction "E_3") (pintype "passive"))
      (node (ref "VT4") (pin "3") (pinfunction "E_3") (pintype "passive"))
      (node (ref "VT5") (pin "3") (pinfunction "E_3") (pintype "passive"))
      (node (ref "XS7") (pin "P$2") (pinfunction "2_P$2") (pintype "passive"))
    )
    (net (code "28") (name "Net-(C5-Pad1)") (class "Default")
      (node (ref "C5") (pin "1") (pinfunction "1_1") (pintype "passive"))
      (node (ref "R17") (pin "2") (pinfunction "2_2") (pintype "passive"))
      (node (ref "R87") (pin "2") (pinfunction "2_2") (pintype "passive"))
      (node (ref "SA6") (pin "P$1") (pinfunction "1_P$1") (pintype "passive"))
      (node (ref "SA6") (pin "P$2") (pinfunction "1_P$2") (pintype "passive"))
    )
    (net (code "29") (name "Net-(C9-Pad1)") (class "Default")
      (node (ref "C9") (pin "1") (pinfunction "1_1") (pintype "passive"))
      (node (ref "R47") (pin "2") (pinfunction "2_2") (pintype "passive"))
      (node (ref "R88") (pin "2") (pinfunction "2_2") (pintype "passive"))
      (node (ref "SA11") (pin "P$1") (pinfunction "1_P$1") (pintype "passive"))
      (node (ref "SA11") (pin "P$2") (pinfunction "1_P$2") (pintype "passive"))
    )
    (net (code "30") (name "Net-(C13-Pad1)") (class "Default")
      (node (ref "C13") (pin "1") (pinfunction "1_1") (pintype "passive"))
      (node (ref "R74") (pin "2") (pinfunction "2_2") (pintype "passive"))
      (node (ref "R89") (pin "2") (pinfunction "2_2") (pintype "passive"))
      (node (ref "SA16") (pin "P$1") (pinfunction "1_P$1") (pintype "passive"))
      (node (ref "SA16") (pin "P$2") (pinfunction "1_P$2") (pintype "passive"))
    )
    (net (code "31") (name "Net-(D1-ANODE)") (class "Default")
      (node (ref "D1") (pin "A") (pinfunction "ANODE_A") (pintype "passive"))
      (node (ref "R5") (pin "1") (pinfunction "1_1") (pintype "passive"))
      (node (ref "R6") (pin "1") (pinfunction "1_1") (pintype "passive"))
      (node (ref "VT3") (pin "2") (pinfunction "B_2") (pintype "passive"))
      (node (ref "VT4") (pin "1") (pinfunction "C_1") (pintype "passive"))
    )
    (net (code "32") (name "Net-(D2-ANODE)") (class "Default")
      (node (ref "D2") (pin "A") (pinfunction "ANODE_A") (pintype "passive"))
      (node (ref "D3") (pin "A") (pinfunction "ANODE_A") (pintype "passive"))
      (node (ref "R7") (pin "1") (pinfunction "1_1") (pintype "passive"))
      (node (ref "VT5") (pin "2") (pinfunction "B_2") (pintype "passive"))
    )
    (net (code "33") (name "Net-(D4-ANODE)") (class "Default")
      (node (ref "C3") (pin "+") (pinfunction "+_+") (pintype "passive"))
      (node (ref "D4") (pin "A") (pinfunction "ANODE_A") (pintype "passive"))
      (node (ref "DA2") (pin "2") (pinfunction "VO_2") (pintype "passive"))
      (node (ref "R11") (pin "2") (pinfunction "2_2") (pintype "passive"))
    )
    (net (code "34") (name "Net-(D4-CATHODE)") (class "Default")
      (node (ref "D4") (pin "C") (pinfunction "CATHODE_C") (pintype "passive"))
      (node (ref "R10") (pin "1") (pinfunction "1_1") (pintype "passive"))
      (node (ref "R10") (pin "3") (pinfunction "1_3") (pintype "passive"))
      (node (ref "VT6") (pin "3") (pinfunction "D_3") (pintype "passive"))
    )
    (net (code "35") (name "Net-(D5-ANODE)") (class "Default")
      (node (ref "C4") (pin "+") (pinfunction "+_+") (pintype "passive"))
      (node (ref "D5") (pin "A") (pinfunction "ANODE_A") (pintype "passive"))
      (node (ref "DA3") (pin "2") (pinfunction "VO_2") (pintype "passive"))
      (node (ref "R13") (pin "2") (pinfunction "2_2") (pintype "passive"))
    )
    (net (code "36") (name "Net-(D5-CATHODE)") (class "Default")
      (node (ref "D5") (pin "C") (pinfunction "CATHODE_C") (pintype "passive"))
      (node (ref "VT7") (pin "3") (pinfunction "D_3") (pintype "passive"))
      (node (ref "XS1") (pin "P$1") (pinfunction "1_P$1") (pintype "passive"))
      (node (ref "XS2") (pin "1") (pinfunction "1_1") (pintype "passive"))
    )
    (net (code "37") (name "Net-(D6-ANODE)") (class "Default")
      (node (ref "D6") (pin "A") (pinfunction "ANODE_A") (pintype "passive"))
      (node (ref "R32") (pin "1") (pinfunction "1_1") (pintype "passive"))
      (node (ref "R33") (pin "1") (pinfunction "1_1") (pintype "passive"))
      (node (ref "VT10") (pin "2") (pinfunction "B_2") (pintype "passive"))
      (node (ref "VT11") (pin "1") (pinfunction "C_1") (pintype "passive"))
    )
    (net (code "38") (name "Net-(D7-ANODE)") (class "Default")
      (node (ref "D7") (pin "A") (pinfunction "ANODE_A") (pintype "passive"))
      (node (ref "D8") (pin "A") (pinfunction "ANODE_A") (pintype "passive"))
      (node (ref "R34") (pin "1") (pinfunction "1_1") (pintype "passive"))
      (node (ref "VT12") (pin "2") (pinfunction "B_2") (pintype "passive"))
    )
    (net (code "39") (name "Net-(D9-ANODE)") (class "Default")
      (node (ref "C7") (pin "+") (pinfunction "+_+") (pintype "passive"))
      (node (ref "D9") (pin "A") (pinfunction "ANODE_A") (pintype "passive"))
      (node (ref "DA4") (pin "2") (pinfunction "VO_2") (pintype "passive"))
      (node (ref "R38") (pin "2") (pinfunction "2_2") (pintype "passive"))
    )
    (net (code "40") (name "Net-(D9-CATHODE)") (class "Default")
      (node (ref "D9") (pin "C") (pinfunction "CATHODE_C") (pintype "passive"))
      (node (ref "R37") (pin "1") (pinfunction "1_1") (pintype "passive"))
      (node (ref "R37") (pin "3") (pinfunction "1_3") (pintype "passive"))
      (node (ref "VT13") (pin "3") (pinfunction "D_3") (pintype "passive"))
    )
    (net (code "41") (name "Net-(D10-ANODE)") (class "Default")
      (node (ref "C8") (pin "+") (pinfunction "+_+") (pintype "passive"))
      (node (ref "D10") (pin "A") (pinfunction "ANODE_A") (pintype "passive"))
      (node (ref "DA5") (pin "2") (pinfunction "VO_2") (pintype "passive"))
      (node (ref "R40") (pin "2") (pinfunction "2_2") (pintype "passive"))
    )
    (net (code "42") (name "Net-(D10-CATHODE)") (class "Default")
      (node (ref "D10") (pin "C") (pinfunction "CATHODE_C") (pintype "passive"))
      (node (ref "VT14") (pin "3") (pinfunction "D_3") (pintype "passive"))
      (node (ref "XS3") (pin "P$1") (pinfunction "1_P$1") (pintype "passive"))
      (node (ref "XS4") (pin "1") (pinfunction "1_1") (pintype "passive"))
    )
    (net (code "43") (name "Net-(D11-ANODE)") (class "Default")
      (node (ref "D11") (pin "A") (pinfunction "ANODE_A") (pintype "passive"))
      (node (ref "R62") (pin "1") (pinfunction "1_1") (pintype "passive"))
      (node (ref "R63") (pin "1") (pinfunction "1_1") (pintype "passive"))
      (node (ref "VT17") (pin "2") (pinfunction "B_2") (pintype "passive"))
      (node (ref "VT18") (pin "1") (pinfunction "C_1") (pintype "passive"))
    )
    (net (code "44") (name "Net-(D12-ANODE)") (class "Default")
      (node (ref "D12") (pin "A") (pinfunction "ANODE_A") (pintype "passive"))
      (node (ref "D13") (pin "A") (pinfunction "ANODE_A") (pintype "passive"))
      (node (ref "R64") (pin "1") (pinfunction "1_1") (pintype "passive"))
      (node (ref "VT19") (pin "2") (pinfunction "B_2") (pintype "passive"))
    )
    (net (code "45") (name "Net-(D14-ANODE)") (class "Default")
      (node (ref "C11") (pin "+") (pinfunction "+_+") (pintype "passive"))
      (node (ref "D14") (pin "A") (pinfunction "ANODE_A") (pintype "passive"))
      (node (ref "DA6") (pin "2") (pinfunction "VO_2") (pintype "passive"))
      (node (ref "R68") (pin "2") (pinfunction "2_2") (pintype "passive"))
    )
    (net (code "46") (name "Net-(D14-CATHODE)") (class "Default")
      (node (ref "D14") (pin "C") (pinfunction "CATHODE_C") (pintype "passive"))
      (node (ref "R67") (pin "1") (pinfunction "1_1") (pintype "passive"))
      (node (ref "R67") (pin "3") (pinfunction "1_3") (pintype "passive"))
      (node (ref "VT20") (pin "3") (pinfunction "D_3") (pintype "passive"))
    )
    (net (code "47") (name "Net-(D15-ANODE)") (class "Default")
      (node (ref "C12") (pin "+") (pinfunction "+_+") (pintype "passive"))
      (node (ref "D15") (pin "A") (pinfunction "ANODE_A") (pintype "passive"))
      (node (ref "DA7") (pin "2") (pinfunction "VO_2") (pintype "passive"))
      (node (ref "R70") (pin "2") (pinfunction "2_2") (pintype "passive"))
    )
    (net (code "48") (name "Net-(D15-CATHODE)") (class "Default")
      (node (ref "D15") (pin "C") (pinfunction "CATHODE_C") (pintype "passive"))
      (node (ref "VT21") (pin "3") (pinfunction "D_3") (pintype "passive"))
      (node (ref "XS5") (pin "P$1") (pinfunction "1_P$1") (pintype "passive"))
      (node (ref "XS6") (pin "1") (pinfunction "1_1") (pintype "passive"))
    )
    (net (code "49") (name "Net-(DA1-ADJ)") (class "Default")
      (node (ref "DA1") (pin "1") (pinfunction "ADJ_1") (pintype "passive"))
      (node (ref "R1") (pin "1") (pinfunction "1_1") (pintype "passive"))
      (node (ref "R2") (pin "2") (pinfunction "2_2") (pintype "passive"))
    )
    (net (code "50") (name "Net-(DA2-ADJ)") (class "Default")
      (node (ref "DA2") (pin "1") (pinfunction "ADJ_1") (pintype "passive"))
      (node (ref "R15") (pin "2") (pinfunction "S_2") (pintype "passive"))
    )
    (net (code "51") (name "Net-(DA2-VI)") (class "Default")
      (node (ref "DA2") (pin "3") (pinfunction "VI_3") (pintype "input"))
      (node (ref "R12") (pin "2") (pinfunction "2_2") (pintype "passive"))
      (node (ref "R20") (pin "1") (pinfunction "1_1") (pintype "passive"))
      (node (ref "VT1") (pin "3") (pinfunction "D_3") (pintype "passive"))
    )
    (net (code "52") (name "Net-(DA3-ADJ)") (class "Default")
      (node (ref "DA3") (pin "1") (pinfunction "ADJ_1") (pintype "passive"))
      (node (ref "R16") (pin "2") (pinfunction "S_2") (pintype "passive"))
    )
    (net (code "53") (name "Net-(DA3-VI)") (class "Default")
      (node (ref "DA3") (pin "3") (pinfunction "VI_3") (pintype "input"))
      (node (ref "R14") (pin "2") (pinfunction "2_2") (pintype "passive"))
      (node (ref "R18") (pin "2") (pinfunction "2_2") (pintype "passive"))
      (node (ref "VT2") (pin "3") (pinfunction "D_3") (pintype "passive"))
    )
    (net (code "54") (name "Net-(DA4-ADJ)") (class "Default")
      (node (ref "DA4") (pin "1") (pinfunction "ADJ_1") (pintype "passive"))
      (node (ref "R45") (pin "2") (pinfunction "S_2") (pintype "passive"))
    )
    (net (code "55") (name "Net-(DA4-VI)") (class "Default")
      (node (ref "DA4") (pin "3") (pinfunction "VI_3") (pintype "input"))
      (node (ref "R39") (pin "2") (pinfunction "2_2") (pintype "passive"))
      (node (ref "R50") (pin "1") (pinfunction "1_1") (pintype "passive"))
      (node (ref "VT8") (pin "3") (pinfunction "D_3") (pintype "passive"))
    )
    (net (code "56") (name "Net-(DA5-ADJ)") (class "Default")
      (node (ref "DA5") (pin "1") (pinfunction "ADJ_1") (pintype "passive"))
      (node (ref "R46") (pin "2") (pinfunction "S_2") (pintype "passive"))
    )
    (net (code "57") (name "Net-(DA5-VI)") (class "Default")
      (node (ref "DA5") (pin "3") (pinfunction "VI_3") (pintype "input"))
      (node (ref "R41") (pin "2") (pinfunction "2_2") (pintype "passive"))
      (node (ref "R48") (pin "2") (pinfunction "2_2") (pintype "passive"))
      (node (ref "VT9") (pin "3") (pinfunction "D_3") (pintype "passive"))
    )
    (net (code "58") (name "Net-(DA6-ADJ)") (class "Default")
      (node (ref "DA6") (pin "1") (pinfunction "ADJ_1") (pintype "passive"))
      (node (ref "R72") (pin "2") (pinfunction "S_2") (pintype "passive"))
    )
    (net (code "59") (name "Net-(DA6-VI)") (class "Default")
      (node (ref "DA6") (pin "3") (pinfunction "VI_3") (pintype "input"))
      (node (ref "R69") (pin "2") (pinfunction "2_2") (pintype "passive"))
      (node (ref "R77") (pin "1") (pinfunction "1_1") (pintype "passive"))
      (node (ref "VT15") (pin "3") (pinfunction "D_3") (pintype "passive"))
    )
    (net (code "60") (name "Net-(DA7-ADJ)") (class "Default")
      (node (ref "DA7") (pin "1") (pinfunction "ADJ_1") (pintype "passive"))
      (node (ref "R73") (pin "2") (pinfunction "S_2") (pintype "passive"))
    )
    (net (code "61") (name "Net-(DA7-VI)") (class "Default")
      (node (ref "DA7") (pin "3") (pinfunction "VI_3") (pintype "input"))
      (node (ref "R71") (pin "2") (pinfunction "2_2") (pintype "passive"))
      (node (ref "R75") (pin "2") (pinfunction "2_2") (pintype "passive"))
      (node (ref "VT16") (pin "3") (pinfunction "D_3") (pintype "passive"))
    )
    (net (code "62") (name "Net-(DD1-PA8)") (class "Default")
      (node (ref "DD1") (pin "P$5") (pinfunction "PA8_P$5") (pintype "bidirectional"))
      (node (ref "JP1") (pin "3") (pinfunction "3_3") (pintype "passive"))
    )
    (net (code "63") (name "Net-(DD1-PA9)") (class "Default")
      (node (ref "DD1") (pin "P$6") (pinfunction "PA9_P$6") (pintype "bidirectional"))
      (node (ref "JP1") (pin "2") (pinfunction "2_2") (pintype "passive"))
    )
    (net (code "64") (name "Net-(DD1-PA10)") (class "Default")
      (node (ref "DD1") (pin "P$7") (pinfunction "PA10_P$7") (pintype "bidirectional"))
      (node (ref "JP1") (pin "1") (pinfunction "1_1") (pintype "passive"))
    )
    (net (code "65") (name "Net-(DD1-PB8)") (class "Default")
      (node (ref "DD1") (pin "P$16") (pinfunction "PB8_P$16") (pintype "bidirectional"))
      (node (ref "U$1") (pin "3") (pinfunction "SCL_3") (pintype "bidirectional"))
    )
    (net (code "66") (name "Net-(DD1-PB9)") (class "Default")
      (node (ref "DD1") (pin "P$17") (pinfunction "PB9_P$17") (pintype "bidirectional"))
      (node (ref "U$1") (pin "4") (pinfunction "SDA_4") (pintype "bidirectional"))
    )
    (net (code "67") (name "Net-(F1-Pad1)") (class "Default")
      (node (ref "F1") (pin "1") (pinfunction "1_1") (pintype "passive"))
      (node (ref "J1") (pin "1") (pinfunction "1_1") (pintype "passive"))
    )
    (net (code "68") (name "Net-(IC1A-+IN)") (class "Default")
      (node (ref "IC1") (pin "3") (pinfunction "+IN_3") (pintype "input"))
      (node (ref "R25") (pin "2") (pinfunction "2_2") (pintype "passive"))
      (node (ref "VT7") (pin "2") (pinfunction "S_2") (pintype "passive"))
    )
    (net (code "69") (name "Net-(IC1A--IN)") (class "Default")
      (node (ref "IC1") (pin "2") (pinfunction "-IN_2") (pintype "input"))
      (node (ref "R28") (pin "2") (pinfunction "2_2") (pintype "passive"))
      (node (ref "R29") (pin "1") (pinfunction "1_1") (pintype "passive"))
    )
    (net (code "70") (name "Net-(IC1B-+IN)") (class "Default")
      (node (ref "IC1") (pin "5") (pinfunction "+IN_5") (pintype "input"))
      (node (ref "R24") (pin "2") (pinfunction "2_2") (pintype "passive"))
      (node (ref "VT6") (pin "2") (pinfunction "S_2") (pintype "passive"))
    )
    (net (code "71") (name "Net-(IC1B--IN)") (class "Default")
      (node (ref "IC1") (pin "6") (pinfunction "-IN_6") (pintype "input"))
      (node (ref "R26") (pin "2") (pinfunction "2_2") (pintype "passive"))
      (node (ref "R27") (pin "1") (pinfunction "1_1") (pintype "passive"))
    )
    (net (code "72") (name "Net-(IC2A-+IN)") (class "Default")
      (node (ref "IC2") (pin "3") (pinfunction "+IN_3") (pintype "input"))
      (node (ref "R55") (pin "2") (pinfunction "2_2") (pintype "passive"))
      (node (ref "VT14") (pin "2") (pinfunction "S_2") (pintype "passive"))
    )
    (net (code "73") (name "Net-(IC2A--IN)") (class "Default")
      (node (ref "IC2") (pin "2") (pinfunction "-IN_2") (pintype "input"))
      (node (ref "R58") (pin "2") (pinfunction "2_2") (pintype "passive"))
      (node (ref "R59") (pin "1") (pinfunction "1_1") (pintype "passive"))
    )
    (net (code "74") (name "Net-(IC2B-+IN)") (class "Default")
      (node (ref "IC2") (pin "5") (pinfunction "+IN_5") (pintype "input"))
      (node (ref "R54") (pin "2") (pinfunction "2_2") (pintype "passive"))
      (node (ref "VT13") (pin "2") (pinfunction "S_2") (pintype "passive"))
    )
    (net (code "75") (name "Net-(IC2B--IN)") (class "Default")
      (node (ref "IC2") (pin "6") (pinfunction "-IN_6") (pintype "input"))
      (node (ref "R56") (pin "2") (pinfunction "2_2") (pintype "passive"))
      (node (ref "R57") (pin "1") (pinfunction "1_1") (pintype "passive"))
    )
    (net (code "76") (name "Net-(IC3A-+IN)") (class "Default")
      (node (ref "IC3") (pin "3") (pinfunction "+IN_3") (pintype "input"))
      (node (ref "R82") (pin "2") (pinfunction "2_2") (pintype "passive"))
      (node (ref "VT21") (pin "2") (pinfunction "S_2") (pintype "passive"))
    )
    (net (code "77") (name "Net-(IC3A--IN)") (class "Default")
      (node (ref "IC3") (pin "2") (pinfunction "-IN_2") (pintype "input"))
      (node (ref "R85") (pin "2") (pinfunction "2_2") (pintype "passive"))
      (node (ref "R86") (pin "1") (pinfunction "1_1") (pintype "passive"))
    )
    (net (code "78") (name "Net-(IC3B-+IN)") (class "Default")
      (node (ref "IC3") (pin "5") (pinfunction "+IN_5") (pintype "input"))
      (node (ref "R81") (pin "2") (pinfunction "2_2") (pintype "passive"))
      (node (ref "VT20") (pin "2") (pinfunction "S_2") (pintype "passive"))
    )
    (net (code "79") (name "Net-(IC3B--IN)") (class "Default")
      (node (ref "IC3") (pin "6") (pinfunction "-IN_6") (pintype "input"))
      (node (ref "R83") (pin "2") (pinfunction "2_2") (pintype "passive"))
      (node (ref "R84") (pin "1") (pinfunction "1_1") (pintype "passive"))
    )
    (net (code "80") (name "Net-(LED1-PadA)") (class "Default")
      (node (ref "LED1") (pin "A") (pinfunction "A_A") (pintype "passive"))
      (node (ref "R12") (pin "1") (pinfunction "1_1") (pintype "passive"))
    )
    (net (code "81") (name "Net-(LED2-PadA)") (class "Default")
      (node (ref "LED2") (pin "A") (pinfunction "A_A") (pintype "passive"))
      (node (ref "R14") (pin "1") (pinfunction "1_1") (pintype "passive"))
    )
    (net (code "82") (name "Net-(LED3-PadA)") (class "Default")
      (node (ref "LED3") (pin "A") (pinfunction "A_A") (pintype "passive"))
      (node (ref "R39") (pin "1") (pinfunction "1_1") (pintype "passive"))
    )
    (net (code "83") (name "Net-(LED4-PadA)") (class "Default")
      (node (ref "LED4") (pin "A") (pinfunction "A_A") (pintype "passive"))
      (node (ref "R41") (pin "1") (pinfunction "1_1") (pintype "passive"))
    )
    (net (code "84") (name "Net-(LED5-PadA)") (class "Default")
      (node (ref "LED5") (pin "A") (pinfunction "A_A") (pintype "passive"))
      (node (ref "R69") (pin "1") (pinfunction "1_1") (pintype "passive"))
    )
    (net (code "85") (name "Net-(LED6-PadA)") (class "Default")
      (node (ref "LED6") (pin "A") (pinfunction "A_A") (pintype "passive"))
      (node (ref "R71") (pin "1") (pinfunction "1_1") (pintype "passive"))
    )
    (net (code "86") (name "Net-(R10B-2)") (class "Default")
      (node (ref "R10") (pin "4") (pinfunction "2_4") (pintype "passive"))
      (node (ref "SA5") (pin "1$P") (pinfunction "P_1$P") (pintype "passive"))
    )
    (net (code "87") (name "Net-(R15-E)") (class "Default")
      (node (ref "R11") (pin "1") (pinfunction "1_1") (pintype "passive"))
      (node (ref "R15") (pin "3") (pinfunction "E_3") (pintype "passive"))
    )
    (net (code "88") (name "Net-(R16-E)") (class "Default")
      (node (ref "R13") (pin "1") (pinfunction "1_1") (pintype "passive"))
      (node (ref "R16") (pin "3") (pinfunction "E_3") (pintype "passive"))
    )
    (net (code "89") (name "Net-(R19-Pad1)") (class "Default")
      (node (ref "R19") (pin "1") (pinfunction "1_1") (pintype "passive"))
      (node (ref "R21") (pin "2") (pinfunction "2_2") (pintype "passive"))
    )
    (net (code "90") (name "Net-(R37B-2)") (class "Default")
      (node (ref "R37") (pin "4") (pinfunction "2_4") (pintype "passive"))
      (node (ref "SA10") (pin "1$P") (pinfunction "P_1$P") (pintype "passive"))
    )
    (net (code "91") (name "Net-(R45-E)") (class "Default")
      (node (ref "R38") (pin "1") (pinfunction "1_1") (pintype "passive"))
      (node (ref "R45") (pin "3") (pinfunction "E_3") (pintype "passive"))
    )
    (net (code "92") (name "Net-(R46-E)") (class "Default")
      (node (ref "R40") (pin "1") (pinfunction "1_1") (pintype "passive"))
      (node (ref "R46") (pin "3") (pinfunction "E_3") (pintype "passive"))
    )
    (net (code "93") (name "Net-(R49-Pad1)") (class "Default")
      (node (ref "R49") (pin "1") (pinfunction "1_1") (pintype "passive"))
      (node (ref "R51") (pin "2") (pinfunction "2_2") (pintype "passive"))
    )
    (net (code "94") (name "Net-(R67B-2)") (class "Default")
      (node (ref "R67") (pin "4") (pinfunction "2_4") (pintype "passive"))
      (node (ref "SA15") (pin "1$P") (pinfunction "P_1$P") (pintype "passive"))
    )
    (net (code "95") (name "Net-(R72-E)") (class "Default")
      (node (ref "R68") (pin "1") (pinfunction "1_1") (pintype "passive"))
      (node (ref "R72") (pin "3") (pinfunction "E_3") (pintype "passive"))
    )
    (net (code "96") (name "Net-(R73-E)") (class "Default")
      (node (ref "R70") (pin "1") (pinfunction "1_1") (pintype "passive"))
      (node (ref "R73") (pin "3") (pinfunction "E_3") (pintype "passive"))
    )
    (net (code "97") (name "Net-(R76-Pad1)") (class "Default")
      (node (ref "R76") (pin "1") (pinfunction "1_1") (pintype "passive"))
      (node (ref "R78") (pin "2") (pinfunction "2_2") (pintype "passive"))
    )
    (net (code "98") (name "Net-(SA1-P)") (class "Default")
      (node (ref "F1") (pin "2") (pinfunction "2_2") (pintype "passive"))
      (node (ref "SA1") (pin "3") (pinfunction "P_3") (pintype "passive"))
    )
    (net (code "99") (name "Net-(SA2-S)") (class "Default")
      (node (ref "C6") (pin "1") (pinfunction "1_1") (pintype "passive"))
      (node (ref "SA2") (pin "1$S") (pinfunction "S_1$S") (pintype "passive"))
      (node (ref "SA4") (pin "1$P") (pinfunction "P_1$P") (pintype "passive"))
    )
    (net (code "100") (name "Net-(SA3-P)") (class "Default")
      (node (ref "R10") (pin "2") (pinfunction "2_2") (pintype "passive"))
      (node (ref "SA3") (pin "1$P") (pinfunction "P_1$P") (pintype "passive"))
    )
    (net (code "101") (name "Net-(SA3-S)") (class "Default")
      (node (ref "SA3") (pin "1$S") (pinfunction "S_1$S") (pintype "passive"))
      (node (ref "SA5") (pin "1$S") (pinfunction "S_1$S") (pintype "passive"))
      (node (ref "XS1") (pin "P$2") (pinfunction "2_P$2") (pintype "passive"))
      (node (ref "XS2") (pin "2") (pinfunction "2_2") (pintype "passive"))
    )
    (net (code "102") (name "Net-(SA4-O)") (class "Default")
      (node (ref "R8") (pin "1") (pinfunction "1_1") (pintype "passive"))
      (node (ref "SA4") (pin "1$O") (pinfunction "O_1$O") (pintype "passive"))
    )
    (net (code "103") (name "Net-(SA7-S)") (class "Default")
      (node (ref "C10") (pin "1") (pinfunction "1_1") (pintype "passive"))
      (node (ref "SA7") (pin "1$S") (pinfunction "S_1$S") (pintype "passive"))
      (node (ref "SA9") (pin "1$P") (pinfunction "P_1$P") (pintype "passive"))
    )
    (net (code "104") (name "Net-(SA8-P)") (class "Default")
      (node (ref "R37") (pin "2") (pinfunction "2_2") (pintype "passive"))
      (node (ref "SA8") (pin "1$P") (pinfunction "P_1$P") (pintype "passive"))
    )
    (net (code "105") (name "Net-(SA9-O)") (class "Default")
      (node (ref "R35") (pin "1") (pinfunction "1_1") (pintype "passive"))
      (node (ref "SA9") (pin "1$O") (pinfunction "O_1$O") (pintype "passive"))
    )
    (net (code "106") (name "Net-(SA10-S)") (class "Default")
      (node (ref "SA10") (pin "1$S") (pinfunction "S_1$S") (pintype "passive"))
      (node (ref "SA8") (pin "1$S") (pinfunction "S_1$S") (pintype "passive"))
      (node (ref "XS3") (pin "P$2") (pinfunction "2_P$2") (pintype "passive"))
      (node (ref "XS4") (pin "2") (pinfunction "2_2") (pintype "passive"))
    )
    (net (code "107") (name "Net-(SA12-S)") (class "Default")
      (node (ref "C14") (pin "1") (pinfunction "1_1") (pintype "passive"))
      (node (ref "SA12") (pin "1$S") (pinfunction "S_1$S") (pintype "passive"))
      (node (ref "SA14") (pin "1$P") (pinfunction "P_1$P") (pintype "passive"))
    )
    (net (code "108") (name "Net-(SA13-P)") (class "Default")
      (node (ref "R67") (pin "2") (pinfunction "2_2") (pintype "passive"))
      (node (ref "SA13") (pin "1$P") (pinfunction "P_1$P") (pintype "passive"))
    )
    (net (code "109") (name "Net-(SA13-S)") (class "Default")
      (node (ref "SA13") (pin "1$S") (pinfunction "S_1$S") (pintype "passive"))
      (node (ref "SA15") (pin "1$S") (pinfunction "S_1$S") (pintype "passive"))
      (node (ref "XS5") (pin "P$2") (pinfunction "2_P$2") (pintype "passive"))
      (node (ref "XS6") (pin "2") (pinfunction "2_2") (pintype "passive"))
    )
    (net (code "110") (name "Net-(SA14-O)") (class "Default")
      (node (ref "R65") (pin "1") (pinfunction "1_1") (pintype "passive"))
      (node (ref "SA14") (pin "1$O") (pinfunction "O_1$O") (pintype "passive"))
    )
    (net (code "111") (name "Net-(VT1-G)") (class "Default")
      (node (ref "R3") (pin "1") (pinfunction "1_1") (pintype "passive"))
      (node (ref "VT1") (pin "1") (pinfunction "G_1") (pintype "passive"))
      (node (ref "VT3") (pin "1") (pinfunction "C_1") (pintype "passive"))
    )
    (net (code "112") (name "Net-(VT2-G)") (class "Default")
      (node (ref "R4") (pin "1") (pinfunction "1_1") (pintype "passive"))
      (node (ref "VT2") (pin "1") (pinfunction "G_1") (pintype "passive"))
      (node (ref "VT5") (pin "1") (pinfunction "C_1") (pintype "passive"))
    )
    (net (code "113") (name "Net-(VT4-B)") (class "Default")
      (node (ref "R9") (pin "1") (pinfunction "1_1") (pintype "passive"))
      (node (ref "VT4") (pin "2") (pinfunction "B_2") (pintype "passive"))
    )
    (net (code "114") (name "Net-(VT6-G)") (class "Default")
      (node (ref "R18") (pin "1") (pinfunction "1_1") (pintype "passive"))
      (node (ref "R22") (pin "2") (pinfunction "2_2") (pintype "passive"))
      (node (ref "VT6") (pin "1") (pinfunction "G_1") (pintype "passive"))
    )
    (net (code "115") (name "Net-(VT7-G)") (class "Default")
      (node (ref "R20") (pin "2") (pinfunction "2_2") (pintype "passive"))
      (node (ref "R23") (pin "2") (pinfunction "2_2") (pintype "passive"))
      (node (ref "VT7") (pin "1") (pinfunction "G_1") (pintype "passive"))
    )
    (net (code "116") (name "Net-(VT10-C)") (class "Default")
      (node (ref "R30") (pin "1") (pinfunction "1_1") (pintype "passive"))
      (node (ref "VT10") (pin "1") (pinfunction "C_1") (pintype "passive"))
      (node (ref "VT8") (pin "1") (pinfunction "G_1") (pintype "passive"))
    )
    (net (code "117") (name "Net-(VT11-B)") (class "Default")
      (node (ref "R36") (pin "1") (pinfunction "1_1") (pintype "passive"))
      (node (ref "VT11") (pin "2") (pinfunction "B_2") (pintype "passive"))
    )
    (net (code "118") (name "Net-(VT12-C)") (class "Default")
      (node (ref "R31") (pin "1") (pinfunction "1_1") (pintype "passive"))
      (node (ref "VT12") (pin "1") (pinfunction "C_1") (pintype "passive"))
      (node (ref "VT9") (pin "1") (pinfunction "G_1") (pintype "passive"))
    )
    (net (code "119") (name "Net-(VT13-G)") (class "Default")
      (node (ref "R48") (pin "1") (pinfunction "1_1") (pintype "passive"))
      (node (ref "R52") (pin "2") (pinfunction "2_2") (pintype "passive"))
      (node (ref "VT13") (pin "1") (pinfunction "G_1") (pintype "passive"))
    )
    (net (code "120") (name "Net-(VT14-G)") (class "Default")
      (node (ref "R50") (pin "2") (pinfunction "2_2") (pintype "passive"))
      (node (ref "R53") (pin "2") (pinfunction "2_2") (pintype "passive"))
      (node (ref "VT14") (pin "1") (pinfunction "G_1") (pintype "passive"))
    )
    (net (code "121") (name "Net-(VT15-G)") (class "Default")
      (node (ref "R60") (pin "1") (pinfunction "1_1") (pintype "passive"))
      (node (ref "VT15") (pin "1") (pinfunction "G_1") (pintype "passive"))
      (node (ref "VT17") (pin "1") (pinfunction "C_1") (pintype "passive"))
    )
    (net (code "122") (name "Net-(VT16-G)") (class "Default")
      (node (ref "R61") (pin "1") (pinfunction "1_1") (pintype "passive"))
      (node (ref "VT16") (pin "1") (pinfunction "G_1") (pintype "passive"))
      (node (ref "VT19") (pin "1") (pinfunction "C_1") (pintype "passive"))
    )
    (net (code "123") (name "Net-(VT18-B)") (class "Default")
      (node (ref "R66") (pin "1") (pinfunction "1_1") (pintype "passive"))
      (node (ref "VT18") (pin "2") (pinfunction "B_2") (pintype "passive"))
    )
    (net (code "124") (name "Net-(VT20-G)") (class "Default")
      (node (ref "R75") (pin "1") (pinfunction "1_1") (pintype "passive"))
      (node (ref "R79") (pin "2") (pinfunction "2_2") (pintype "passive"))
      (node (ref "VT20") (pin "1") (pinfunction "G_1") (pintype "passive"))
    )
    (net (code "125") (name "Net-(VT21-G)") (class "Default")
      (node (ref "R77") (pin "2") (pinfunction "2_2") (pintype "passive"))
      (node (ref "R80") (pin "2") (pinfunction "2_2") (pintype "passive"))
      (node (ref "VT21") (pin "1") (pinfunction "G_1") (pintype "passive"))
    )
    (net (code "126") (name "VCC") (class "Default")
      (node (ref "C2") (pin "+") (pinfunction "+_+") (pintype "passive"))
      (node (ref "DA1") (pin "2") (pinfunction "VO_2") (pintype "passive"))
      (node (ref "DD1") (pin "P$20") (pinfunction "3.3V1_P$20") (pintype "bidirectional"))
      (node (ref "DD1") (pin "P$23") (pinfunction "3.3V_P$23") (pintype "bidirectional"))
      (node (ref "R1") (pin "2") (pinfunction "2_2") (pintype "passive"))
      (node (ref "R17") (pin "1") (pinfunction "1_1") (pintype "passive"))
      (node (ref "R19") (pin "3") (pinfunction "2_3") (pintype "passive"))
      (node (ref "R32") (pin "2") (pinfunction "2_2") (pintype "passive"))
      (node (ref "R33") (pin "2") (pinfunction "2_2") (pintype "passive"))
      (node (ref "R34") (pin "2") (pinfunction "2_2") (pintype "passive"))
      (node (ref "R35") (pin "2") (pinfunction "2_2") (pintype "passive"))
      (node (ref "R47") (pin "1") (pinfunction "1_1") (pintype "passive"))
      (node (ref "R49") (pin "3") (pinfunction "2_3") (pintype "passive"))
      (node (ref "R5") (pin "2") (pinfunction "2_2") (pintype "passive"))
      (node (ref "R6") (pin "2") (pinfunction "2_2") (pintype "passive"))
      (node (ref "R62") (pin "2") (pinfunction "2_2") (pintype "passive"))
      (node (ref "R63") (pin "2") (pinfunction "2_2") (pintype "passive"))
      (node (ref "R64") (pin "2") (pinfunction "2_2") (pintype "passive"))
      (node (ref "R65") (pin "2") (pinfunction "2_2") (pintype "passive"))
      (node (ref "R7") (pin "2") (pinfunction "2_2") (pintype "passive"))
      (node (ref "R74") (pin "1") (pinfunction "1_1") (pintype "passive"))
      (node (ref "R76") (pin "3") (pinfunction "2_3") (pintype "passive"))
      (node (ref "R8") (pin "2") (pinfunction "2_2") (pintype "passive"))
      (node (ref "S1") (pin "4") (pinfunction "4_4") (pintype "passive"))
      (node (ref "S1") (pin "5") (pinfunction "5_5") (pintype "passive"))
      (node (ref "S1") (pin "6") (pinfunction "6_6") (pintype "passive"))
      (node (ref "U$1") (pin "2") (pinfunction "VCC_2") (pintype "power_in"))
    )
    (net (code "127") (name "unconnected-(DD1-5V-PadP$18)") (class "Default")
      (node (ref "DD1") (pin "P$18") (pinfunction "5V_P$18") (pintype "bidirectional"))
    )
    (net (code "128") (name "unconnected-(DD1-PB5-PadP$13)") (class "Default")
      (node (ref "DD1") (pin "P$13") (pinfunction "PB5_P$13") (pintype "bidirectional"))
    )
    (net (code "129") (name "unconnected-(DD1-PB6-PadP$14)") (class "Default")
      (node (ref "DD1") (pin "P$14") (pinfunction "PB6_P$14") (pintype "bidirectional"))
    )
    (net (code "130") (name "unconnected-(DD1-PB7-PadP$15)") (class "Default")
      (node (ref "DD1") (pin "P$15") (pinfunction "PB7_P$15") (pintype "bidirectional"))
    )
    (net (code "131") (name "unconnected-(DD1-PC13-PadP$39)") (class "Default")
      (node (ref "DD1") (pin "P$39") (pinfunction "PC13_P$39") (pintype "bidirectional"))
    )
    (net (code "132") (name "unconnected-(DD1-PC14-PadP$38)") (class "Default")
      (node (ref "DD1") (pin "P$38") (pinfunction "PC14_P$38") (pintype "bidirectional"))
    )
    (net (code "133") (name "unconnected-(DD1-PC15-PadP$37)") (class "Default")
      (node (ref "DD1") (pin "P$37") (pinfunction "PC15_P$37") (pintype "bidirectional"))
    )
    (net (code "134") (name "unconnected-(DD1-RESET-PadP$24)") (class "Default")
      (node (ref "DD1") (pin "P$24") (pinfunction "RESET_P$24") (pintype "bidirectional"))
    )
    (net (code "135") (name "unconnected-(DD1-VBAT-PadP$40)") (class "Default")
      (node (ref "DD1") (pin "P$40") (pinfunction "VBAT_P$40") (pintype "bidirectional"))
    )
    (net (code "136") (name "unconnected-(J1-Pad2)") (class "Default")
      (node (ref "J1") (pin "2") (pinfunction "2_2") (pintype "passive"))
    )
    (net (code "137") (name "unconnected-(SA1-S-Pad2)") (class "Default")
      (node (ref "SA1") (pin "2") (pinfunction "S_2") (pintype "passive"))
    )
    (net (code "138") (name "unconnected-(SA3-O-Pad1$O)") (class "Default")
      (node (ref "SA3") (pin "1$O") (pinfunction "O_1$O") (pintype "passive"))
    )
    (net (code "139") (name "unconnected-(SA5-O-Pad1$O)") (class "Default")
      (node (ref "SA5") (pin "1$O") (pinfunction "O_1$O") (pintype "passive"))
    )
    (net (code "140") (name "unconnected-(SA8-O-Pad1$O)") (class "Default")
      (node (ref "SA8") (pin "1$O") (pinfunction "O_1$O") (pintype "passive"))
    )
    (net (code "141") (name "unconnected-(SA10-O-Pad1$O)") (class "Default")
      (node (ref "SA10") (pin "1$O") (pinfunction "O_1$O") (pintype "passive"))
    )
    (net (code "142") (name "unconnected-(SA13-O-Pad1$O)") (class "Default")
      (node (ref "SA13") (pin "1$O") (pinfunction "O_1$O") (pintype "passive"))
    )
    (net (code "143") (name "unconnected-(SA15-O-Pad1$O)") (class "Default")
      (node (ref "SA15") (pin "1$O") (pinfunction "O_1$O") (pintype "passive"))
    )
  )
)
